# mainBoard_GRITSBot3-0_v14.net
KiCad netlist of a schematic drawn in EAGLE
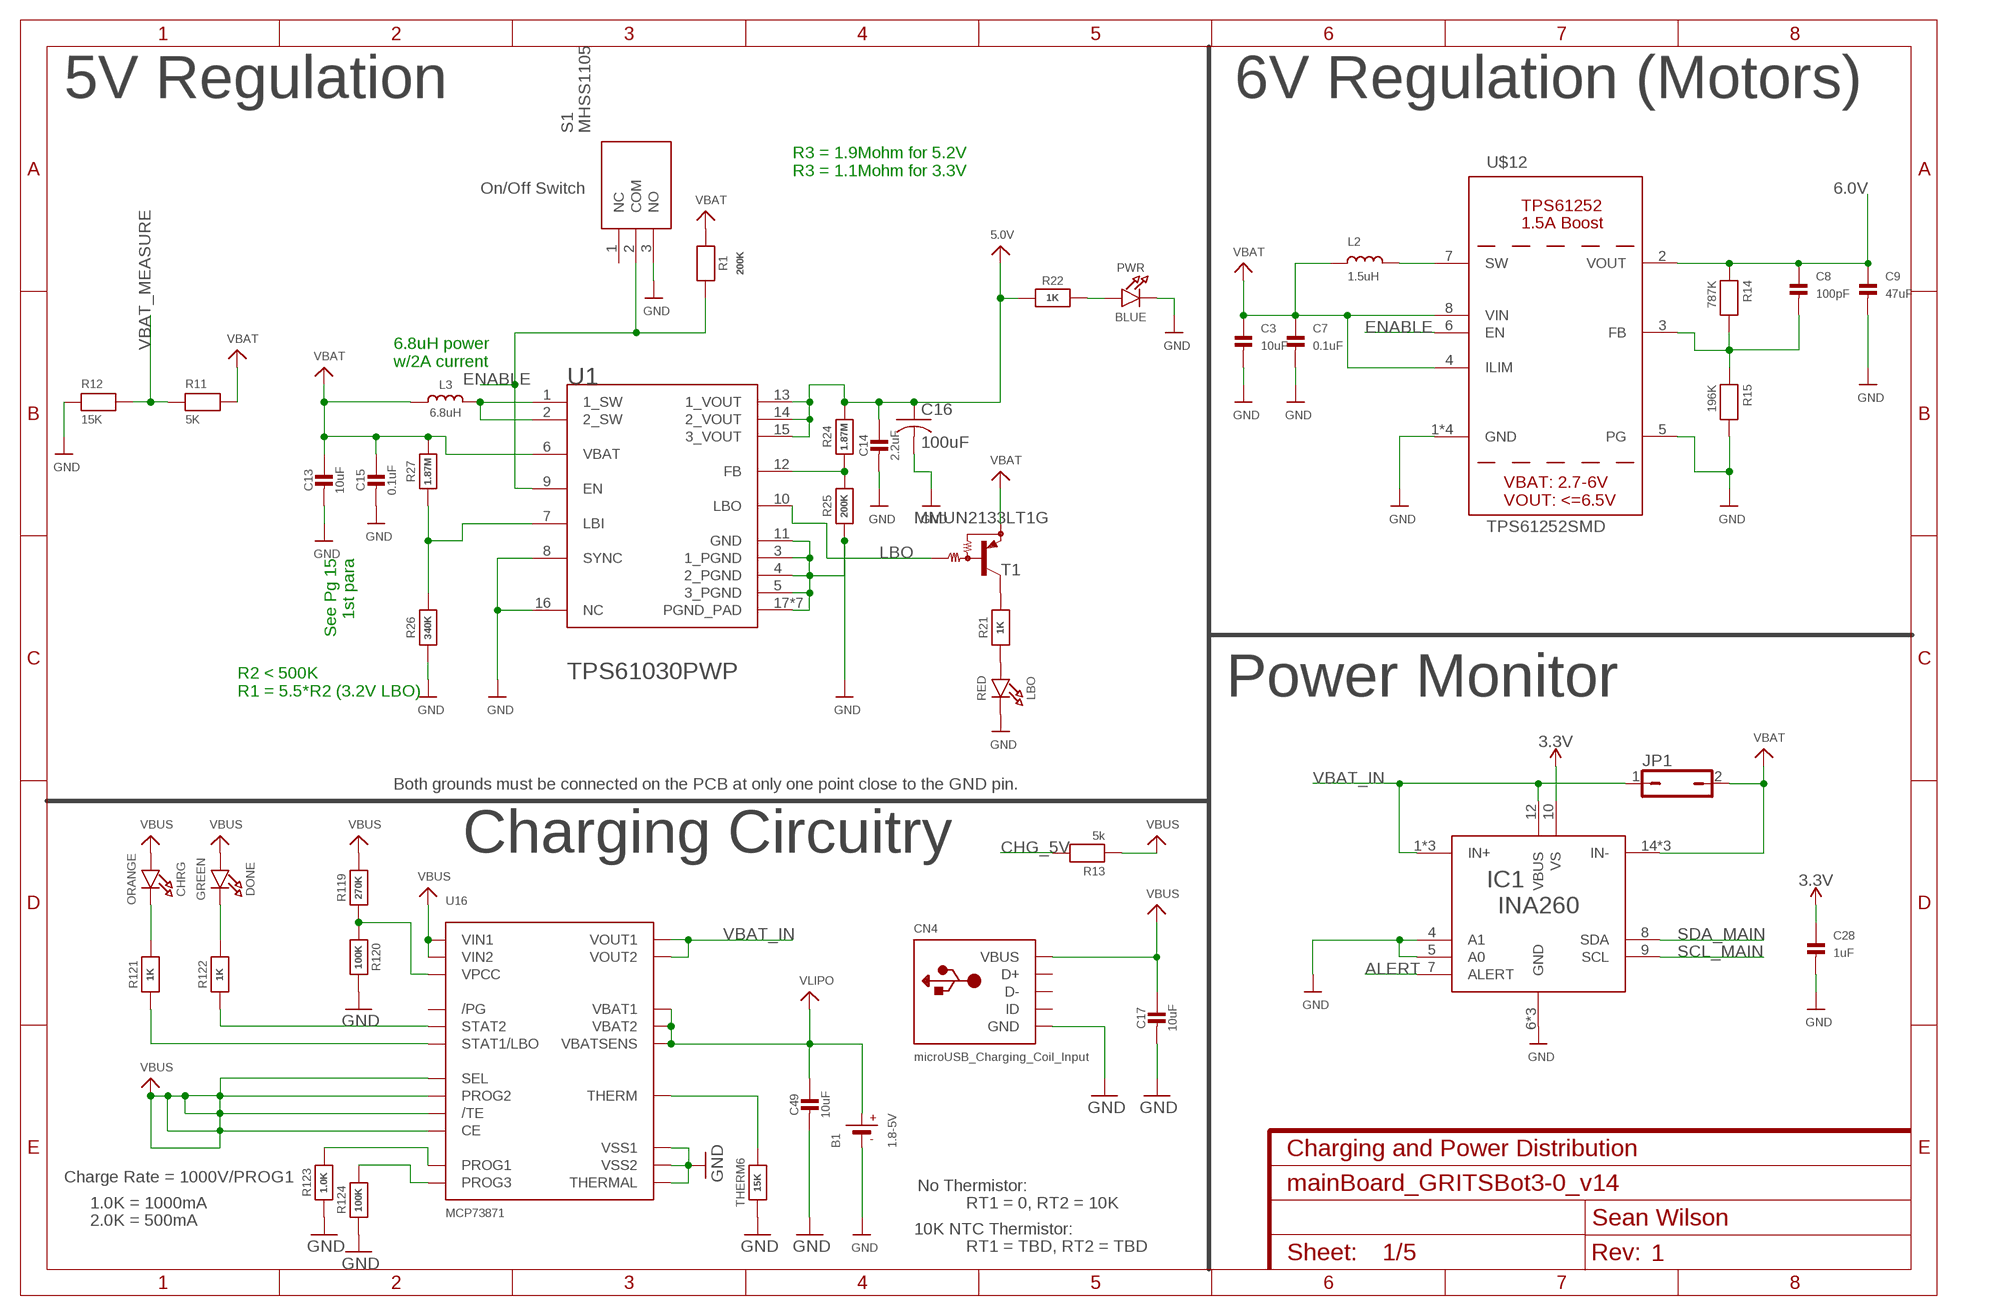
[diagram p0: schematic, sheet 1]
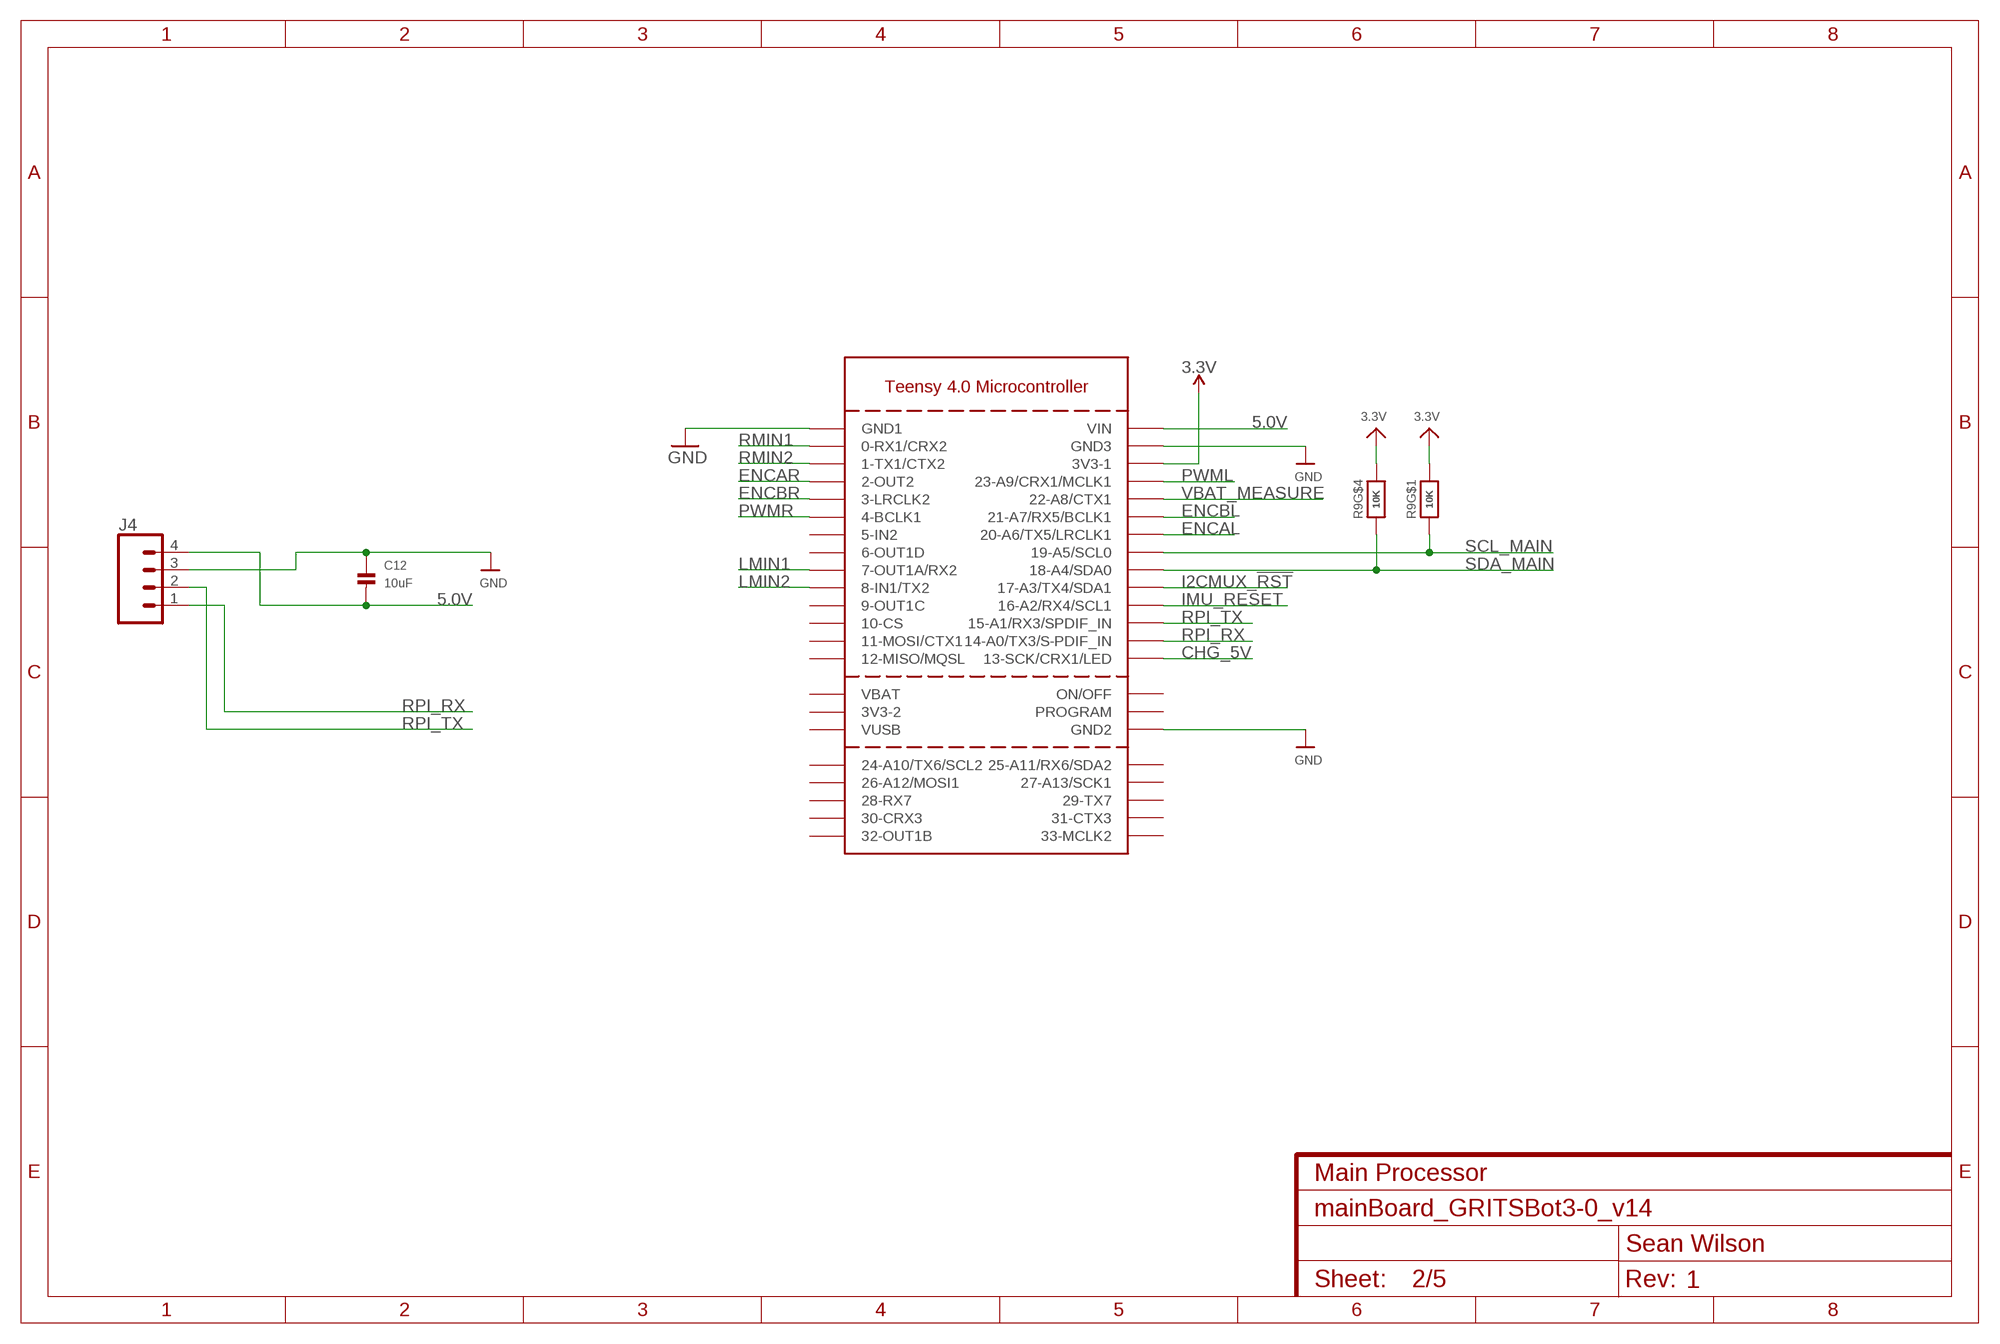
[diagram p1: schematic, sheet 2]
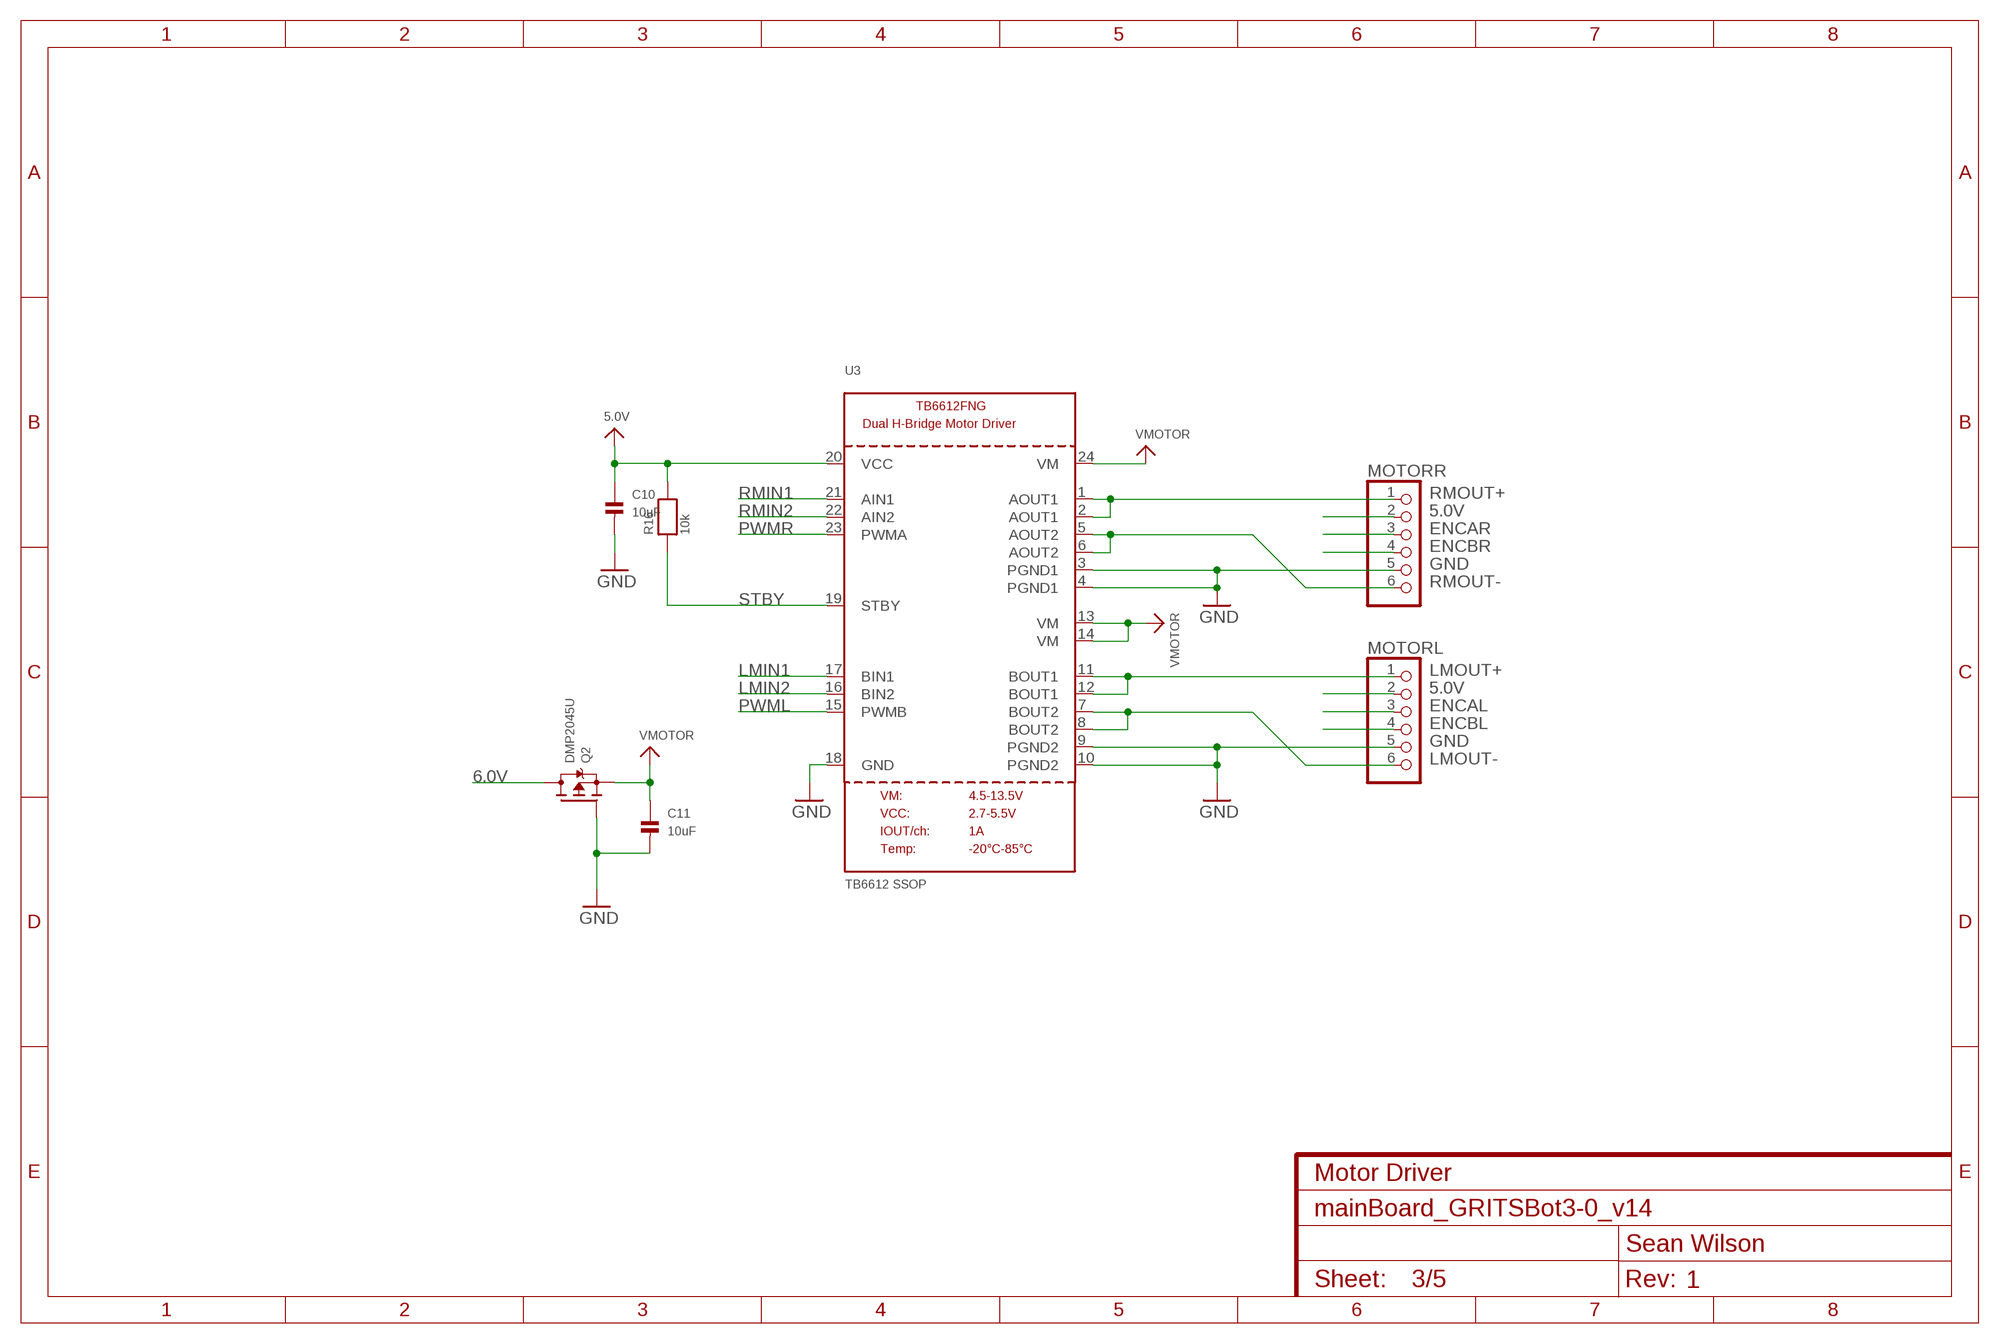
[diagram p2: schematic, sheet 3]
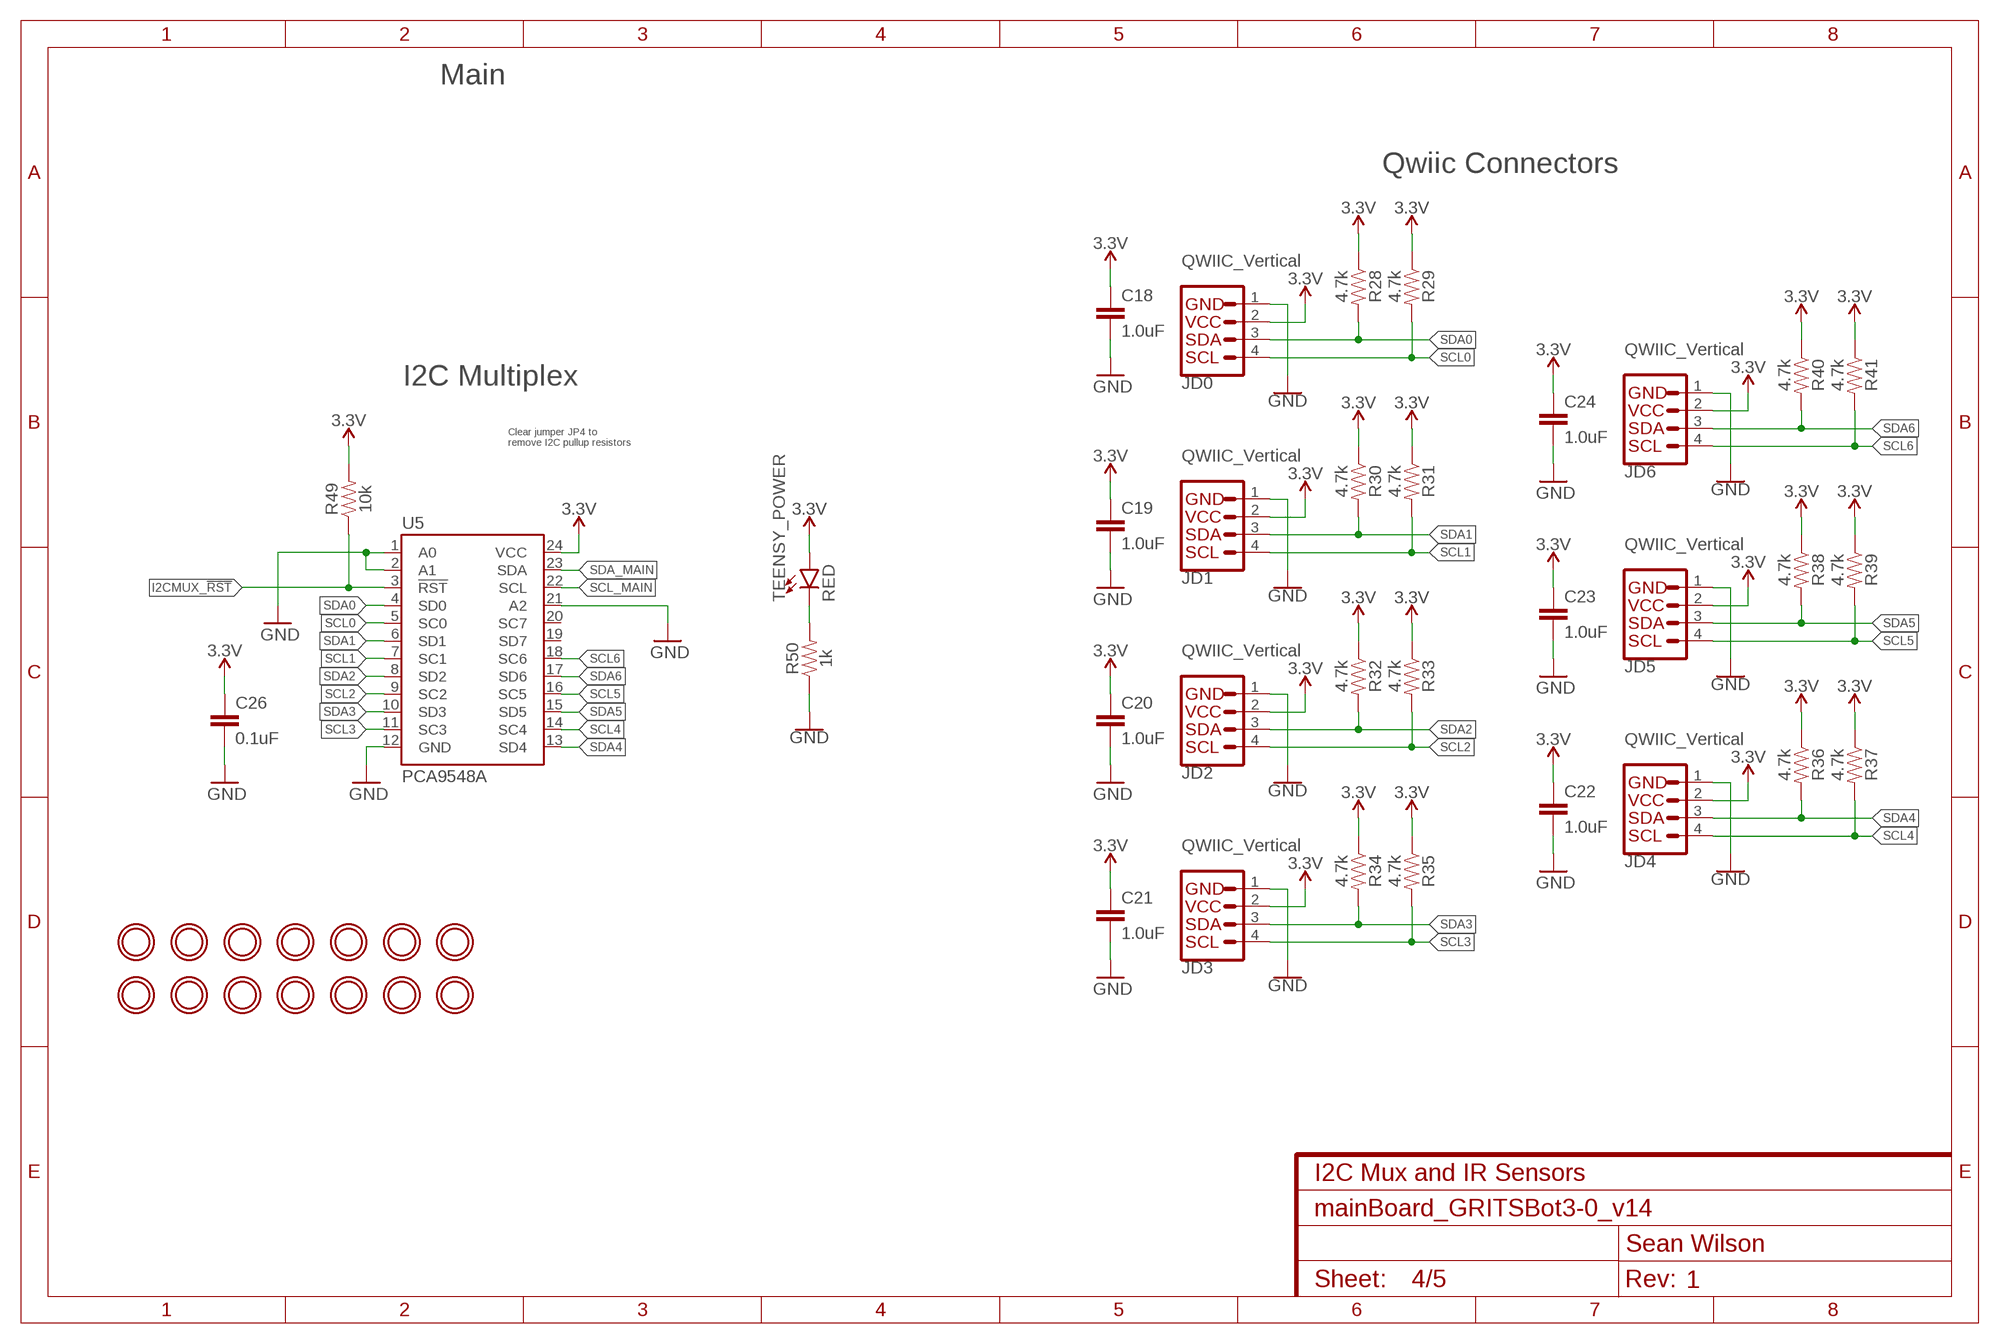
[diagram p3: schematic, sheet 4]
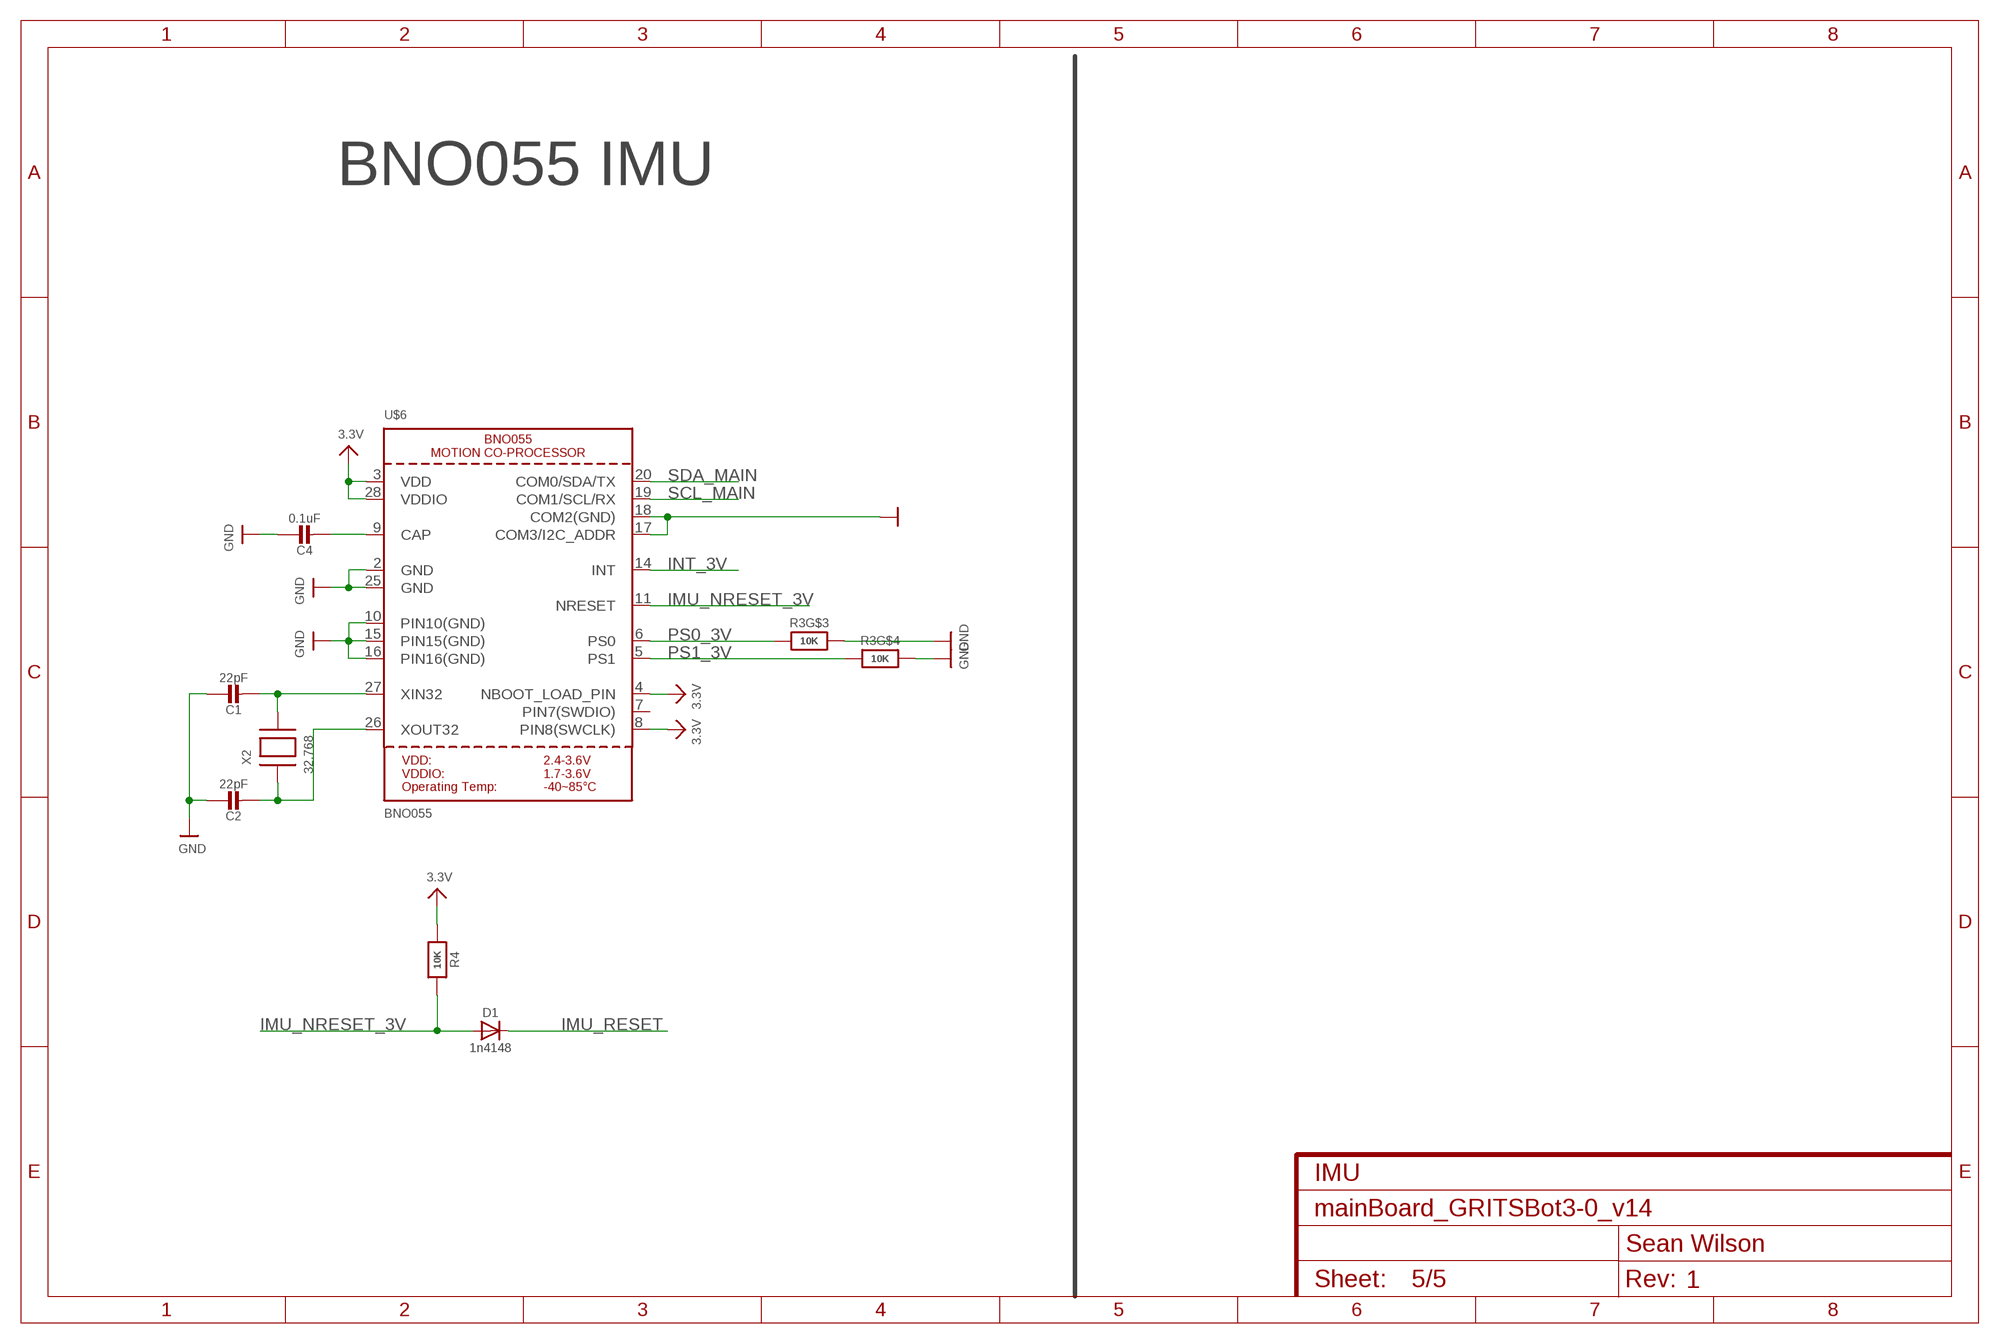
[diagram p4: schematic, sheet 5]

(export (version "E")
  (design (tool "Eeschema 10.0.6"))
  (components
    (comp (ref "C1")
      (value "22pF")
      (footprint "eagle-import:0603-NO")
      (libsource (lib "eagle-import") (part "CAP_CERAMIC0603_NO"))
    )
    (comp (ref "C2")
      (value "22pF")
      (footprint "eagle-import:0603-NO")
      (libsource (lib "eagle-import") (part "CAP_CERAMIC0603_NO"))
    )
    (comp (ref "C4")
      (value "0.1uF")
      (footprint "eagle-import:0603-NO")
      (libsource (lib "eagle-import") (part "CAP_CERAMIC0603_NO"))
    )
    (comp (ref "D1")
      (value "1n4148")
      (footprint "eagle-import:SOD-323")
      (libsource (lib "eagle-import") (part "DIODESOD-323"))
    )
    (comp (ref "R3")
      (value "10K")
      (footprint "eagle-import:RESPACK_4X0603")
      (libsource (lib "eagle-import") (part "RESISTOR_4PACK"))
    )
    (comp (ref "R4")
      (value "10K")
      (footprint "eagle-import:0603-NO")
      (libsource (lib "eagle-import") (part "RESISTOR_0603_NOOUT"))
    )
    (comp (ref "U$6")
      (value "BNO055")
      (footprint "eagle-import:BNO055")
      (libsource (lib "eagle-import") (part "BNO055"))
    )
    (comp (ref "X2")
      (value "32.768")
      (footprint "eagle-import:XTAL3215")
      (libsource (lib "eagle-import") (part "XTAL-3.2X1.5"))
    )
    (comp (ref "C12")
      (value "10uF")
      (footprint "eagle-import:0603")
      (libsource (lib "eagle-import") (part "CAP_CERAMIC0603"))
    )
    (comp (ref "J4")
      (value "CONN_041X04_NO_SILK")
      (footprint "eagle-import:1X04_NO_SILK")
      (libsource (lib "eagle-import") (part "CONN_041X04_NO_SILK"))
    )
    (comp (ref "R9")
      (value "10K")
      (footprint "eagle-import:RESPACK_4X0603")
      (libsource (lib "eagle-import") (part "RESISTOR_4PACK"))
    )
    (comp (ref "U$57")
      (value "TEENSY40")
      (footprint "eagle-import:TEENSY40")
      (libsource (lib "eagle-import") (part "TEENSY40"))
    )
    (comp (ref "C18")
      (value "1.0uF")
      (footprint "eagle-import:0603")
      (libsource (lib "eagle-import") (part "1.0UF-0603-16V-10%"))
    )
    (comp (ref "C19")
      (value "1.0uF")
      (footprint "eagle-import:0603")
      (libsource (lib "eagle-import") (part "1.0UF-0603-16V-10%"))
    )
    (comp (ref "C20")
      (value "1.0uF")
      (footprint "eagle-import:0603")
      (libsource (lib "eagle-import") (part "1.0UF-0603-16V-10%"))
    )
    (comp (ref "C21")
      (value "1.0uF")
      (footprint "eagle-import:0603")
      (libsource (lib "eagle-import") (part "1.0UF-0603-16V-10%"))
    )
    (comp (ref "C22")
      (value "1.0uF")
      (footprint "eagle-import:0603")
      (libsource (lib "eagle-import") (part "1.0UF-0603-16V-10%"))
    )
    (comp (ref "C23")
      (value "1.0uF")
      (footprint "eagle-import:0603")
      (libsource (lib "eagle-import") (part "1.0UF-0603-16V-10%"))
    )
    (comp (ref "C24")
      (value "1.0uF")
      (footprint "eagle-import:0603")
      (libsource (lib "eagle-import") (part "1.0UF-0603-16V-10%"))
    )
    (comp (ref "C26")
      (value "0.1uF")
      (footprint "eagle-import:0603")
      (libsource (lib "eagle-import") (part "0.1UF-0603-25V-(+80/-20%)"))
    )
    (comp (ref "JD0")
      (value "QWIIC_Vertical")
      (footprint "eagle-import:JST04_1MM_VERT")
      (libsource (lib "eagle-import") (part "QWIIC_CONNECTOR"))
    )
    (comp (ref "JD1")
      (value "QWIIC_Vertical")
      (footprint "eagle-import:JST04_1MM_VERT")
      (libsource (lib "eagle-import") (part "QWIIC_CONNECTOR"))
    )
    (comp (ref "JD2")
      (value "QWIIC_Vertical")
      (footprint "eagle-import:JST04_1MM_VERT")
      (libsource (lib "eagle-import") (part "QWIIC_CONNECTOR"))
    )
    (comp (ref "JD3")
      (value "QWIIC_Vertical")
      (footprint "eagle-import:JST04_1MM_VERT")
      (libsource (lib "eagle-import") (part "QWIIC_CONNECTOR"))
    )
    (comp (ref "JD4")
      (value "QWIIC_Vertical")
      (footprint "eagle-import:JST04_1MM_VERT")
      (libsource (lib "eagle-import") (part "QWIIC_CONNECTOR"))
    )
    (comp (ref "JD5")
      (value "QWIIC_Vertical")
      (footprint "eagle-import:JST04_1MM_VERT")
      (libsource (lib "eagle-import") (part "QWIIC_CONNECTOR"))
    )
    (comp (ref "JD6")
      (value "QWIIC_Vertical")
      (footprint "eagle-import:JST04_1MM_VERT")
      (libsource (lib "eagle-import") (part "QWIIC_CONNECTOR"))
    )
    (comp (ref "R28")
      (value "4.7k")
      (footprint "eagle-import:0603")
      (libsource (lib "eagle-import") (part "4.7KOHM-0603-1/10W-1%"))
    )
    (comp (ref "R29")
      (value "4.7k")
      (footprint "eagle-import:0603")
      (libsource (lib "eagle-import") (part "4.7KOHM-0603-1/10W-1%"))
    )
    (comp (ref "R30")
      (value "4.7k")
      (footprint "eagle-import:0603")
      (libsource (lib "eagle-import") (part "4.7KOHM-0603-1/10W-1%"))
    )
    (comp (ref "R31")
      (value "4.7k")
      (footprint "eagle-import:0603")
      (libsource (lib "eagle-import") (part "4.7KOHM-0603-1/10W-1%"))
    )
    (comp (ref "R32")
      (value "4.7k")
      (footprint "eagle-import:0603")
      (libsource (lib "eagle-import") (part "4.7KOHM-0603-1/10W-1%"))
    )
    (comp (ref "R33")
      (value "4.7k")
      (footprint "eagle-import:0603")
      (libsource (lib "eagle-import") (part "4.7KOHM-0603-1/10W-1%"))
    )
    (comp (ref "R34")
      (value "4.7k")
      (footprint "eagle-import:0603")
      (libsource (lib "eagle-import") (part "4.7KOHM-0603-1/10W-1%"))
    )
    (comp (ref "R35")
      (value "4.7k")
      (footprint "eagle-import:0603")
      (libsource (lib "eagle-import") (part "4.7KOHM-0603-1/10W-1%"))
    )
    (comp (ref "R36")
      (value "4.7k")
      (footprint "eagle-import:0603")
      (libsource (lib "eagle-import") (part "4.7KOHM-0603-1/10W-1%"))
    )
    (comp (ref "R37")
      (value "4.7k")
      (footprint "eagle-import:0603")
      (libsource (lib "eagle-import") (part "4.7KOHM-0603-1/10W-1%"))
    )
    (comp (ref "R38")
      (value "4.7k")
      (footprint "eagle-import:0603")
      (libsource (lib "eagle-import") (part "4.7KOHM-0603-1/10W-1%"))
    )
    (comp (ref "R39")
      (value "4.7k")
      (footprint "eagle-import:0603")
      (libsource (lib "eagle-import") (part "4.7KOHM-0603-1/10W-1%"))
    )
    (comp (ref "R40")
      (value "4.7k")
      (footprint "eagle-import:0603")
      (libsource (lib "eagle-import") (part "4.7KOHM-0603-1/10W-1%"))
    )
    (comp (ref "R41")
      (value "4.7k")
      (footprint "eagle-import:0603")
      (libsource (lib "eagle-import") (part "4.7KOHM-0603-1/10W-1%"))
    )
    (comp (ref "R49")
      (value "10k")
      (footprint "eagle-import:0603")
      (libsource (lib "eagle-import") (part "10KOHM-0603-1/10W-1%"))
    )
    (comp (ref "R50")
      (value "1k")
      (footprint "eagle-import:0603")
      (libsource (lib "eagle-import") (part "1KOHM-0603-1/10W-1%"))
    )
    (comp (ref "TEENSY_POWER")
      (value "RED")
      (footprint "eagle-import:LED-0603")
      (libsource (lib "eagle-import") (part "LED-RED0603"))
    )
    (comp (ref "U$8")
      (value "MOUNTINGHOLE2.5")
      (footprint "eagle-import:MOUNTINGHOLE_2.5_PLATED")
      (libsource (lib "eagle-import") (part "MOUNTINGHOLE2.5"))
    )
    (comp (ref "U$30")
      (value "MOUNTINGHOLE2.5")
      (footprint "eagle-import:MOUNTINGHOLE_2.5_PLATED")
      (libsource (lib "eagle-import") (part "MOUNTINGHOLE2.5"))
    )
    (comp (ref "U$31")
      (value "MOUNTINGHOLE2.5")
      (footprint "eagle-import:MOUNTINGHOLE_2.5_PLATED")
      (libsource (lib "eagle-import") (part "MOUNTINGHOLE2.5"))
    )
    (comp (ref "U$32")
      (value "MOUNTINGHOLE2.5")
      (footprint "eagle-import:MOUNTINGHOLE_2.5_PLATED")
      (libsource (lib "eagle-import") (part "MOUNTINGHOLE2.5"))
    )
    (comp (ref "U$33")
      (value "MOUNTINGHOLE2.5")
      (footprint "eagle-import:MOUNTINGHOLE_2.5_PLATED")
      (libsource (lib "eagle-import") (part "MOUNTINGHOLE2.5"))
    )
    (comp (ref "U$34")
      (value "MOUNTINGHOLE2.5")
      (footprint "eagle-import:MOUNTINGHOLE_2.5_PLATED")
      (libsource (lib "eagle-import") (part "MOUNTINGHOLE2.5"))
    )
    (comp (ref "U$35")
      (value "MOUNTINGHOLE2.5")
      (footprint "eagle-import:MOUNTINGHOLE_2.5_PLATED")
      (libsource (lib "eagle-import") (part "MOUNTINGHOLE2.5"))
    )
    (comp (ref "U$36")
      (value "MOUNTINGHOLE2.5")
      (footprint "eagle-import:MOUNTINGHOLE_2.5_PLATED")
      (libsource (lib "eagle-import") (part "MOUNTINGHOLE2.5"))
    )
    (comp (ref "U$37")
      (value "MOUNTINGHOLE2.5")
      (footprint "eagle-import:MOUNTINGHOLE_2.5_PLATED")
      (libsource (lib "eagle-import") (part "MOUNTINGHOLE2.5"))
    )
    (comp (ref "U$43")
      (value "MOUNTINGHOLE2.5")
      (footprint "eagle-import:MOUNTINGHOLE_2.5_PLATED")
      (libsource (lib "eagle-import") (part "MOUNTINGHOLE2.5"))
    )
    (comp (ref "U$45")
      (value "MOUNTINGHOLE2.5")
      (footprint "eagle-import:MOUNTINGHOLE_2.5_PLATED")
      (libsource (lib "eagle-import") (part "MOUNTINGHOLE2.5"))
    )
    (comp (ref "U$46")
      (value "MOUNTINGHOLE2.5")
      (footprint "eagle-import:MOUNTINGHOLE_2.5_PLATED")
      (libsource (lib "eagle-import") (part "MOUNTINGHOLE2.5"))
    )
    (comp (ref "U$47")
      (value "MOUNTINGHOLE2.5")
      (footprint "eagle-import:MOUNTINGHOLE_2.5_PLATED")
      (libsource (lib "eagle-import") (part "MOUNTINGHOLE2.5"))
    )
    (comp (ref "U$48")
      (value "MOUNTINGHOLE2.5")
      (footprint "eagle-import:MOUNTINGHOLE_2.5_PLATED")
      (libsource (lib "eagle-import") (part "MOUNTINGHOLE2.5"))
    )
    (comp (ref "U5")
      (value "PCA9548A")
      (footprint "eagle-import:TSSOP28")
      (libsource (lib "eagle-import") (part "PCA9548A"))
    )
    (comp (ref "B1")
      (value "1.8-5V")
      (footprint "eagle-import:JSTPH2")
      (libsource (lib "eagle-import") (part "BATTERY"))
    )
    (comp (ref "C3")
      (value "10uF")
      (footprint "eagle-import:0603")
      (libsource (lib "eagle-import") (part "CAP_CERAMIC0603"))
    )
    (comp (ref "C7")
      (value "0.1uF")
      (footprint "eagle-import:0805")
      (libsource (lib "eagle-import") (part "CAP_CERAMIC0805"))
    )
    (comp (ref "C8")
      (value "100pF")
      (footprint "eagle-import:0603")
      (libsource (lib "eagle-import") (part "CAP_CERAMIC0603"))
    )
    (comp (ref "C9")
      (value "47uF")
      (footprint "eagle-import:1206")
      (libsource (lib "eagle-import") (part "CAP_CERAMIC1206"))
    )
    (comp (ref "C13")
      (value "10uF")
      (footprint "eagle-import:0805-NO")
      (libsource (lib "eagle-import") (part "CAP_CERAMIC0805-NOOUTLINE"))
    )
    (comp (ref "C14")
      (value "2.2uF")
      (footprint "eagle-import:0805-NO")
      (libsource (lib "eagle-import") (part "CAP_CERAMIC0805-NOOUTLINE"))
    )
    (comp (ref "C15")
      (value "0.1uF")
      (footprint "eagle-import:0805_10MGAP")
      (libsource (lib "eagle-import") (part "CAP_CERAMIC0805_10MGAP"))
    )
    (comp (ref "C16")
      (value "100uF")
      (footprint "eagle-import:C1210")
      (libsource (lib "eagle-import") (part "C-USC1210"))
    )
    (comp (ref "C17")
      (value "10uF")
      (footprint "eagle-import:0805-NO")
      (libsource (lib "eagle-import") (part "CAP_CERAMIC0805-NOOUTLINE"))
    )
    (comp (ref "C28")
      (value "1uF")
      (footprint "eagle-import:0603-NO")
      (libsource (lib "eagle-import") (part "CAP_CERAMIC0603_NO"))
    )
    (comp (ref "C49")
      (value "10uF")
      (footprint "eagle-import:0805-NO")
      (libsource (lib "eagle-import") (part "CAP_CERAMIC0805-NOOUTLINE"))
    )
    (comp (ref "CHRG")
      (value "ORANGE")
      (footprint "eagle-import:CHIPLED_0805_NOOUTLINE")
      (libsource (lib "eagle-import") (part "LED0805_NOOUTLINE"))
    )
    (comp (ref "CN4")
      (value "microUSB_Charging_Coil_Input")
      (footprint "eagle-import:4UCONN_20329")
      (libsource (lib "eagle-import") (part "USBMICRO_20329"))
    )
    (comp (ref "DONE")
      (value "GREEN")
      (footprint "eagle-import:CHIPLED_0805_NOOUTLINE")
      (libsource (lib "eagle-import") (part "LED0805_NOOUTLINE"))
    )
    (comp (ref "IC1")
      (value "INA260")
      (footprint "eagle-import:TSSOP16")
      (libsource (lib "eagle-import") (part "INA260"))
    )
    (comp (ref "JP1")
      (value "JP1Q")
      (footprint "eagle-import:JP1")
      (libsource (lib "eagle-import") (part "JP1Q"))
    )
    (comp (ref "L2")
      (value "1.5uH")
      (footprint "eagle-import:MURATA_DFE252012P-1R5M=P2")
      (libsource (lib "eagle-import") (part "MURATA_DFE252012P-1R5M=P2"))
    )
    (comp (ref "L3")
      (value "6.8uH")
      (footprint "eagle-import:INDUCTOR_5X5MM_TDK_VLC5045")
      (libsource (lib "eagle-import") (part "INDUCTORTDK_VLC5045"))
    )
    (comp (ref "LBO")
      (value "RED")
      (footprint "eagle-import:CHIPLED_0805_NOOUTLINE")
      (libsource (lib "eagle-import") (part "LED0805_NOOUTLINE"))
    )
    (comp (ref "PWR")
      (value "BLUE")
      (footprint "eagle-import:CHIPLED_0805_NOOUTLINE")
      (libsource (lib "eagle-import") (part "LED0805_NOOUTLINE"))
    )
    (comp (ref "R1")
      (value "200K")
      (footprint "eagle-import:0805-NO")
      (libsource (lib "eagle-import") (part "RESISTOR0805_NOOUTLINE"))
    )
    (comp (ref "R11")
      (value "5K")
      (footprint "eagle-import:0805")
      (libsource (lib "eagle-import") (part "RESISTOR0805"))
    )
    (comp (ref "R12")
      (value "15K")
      (footprint "eagle-import:0805")
      (libsource (lib "eagle-import") (part "RESISTOR0805"))
    )
    (comp (ref "R13")
      (value "5k")
      (footprint "eagle-import:0805")
      (libsource (lib "eagle-import") (part "RESISTOR0805"))
    )
    (comp (ref "R14")
      (value "787K")
      (footprint "eagle-import:0805")
      (libsource (lib "eagle-import") (part "RESISTOR0805"))
    )
    (comp (ref "R15")
      (value "196K")
      (footprint "eagle-import:0805")
      (libsource (lib "eagle-import") (part "RESISTOR0805"))
    )
    (comp (ref "R21")
      (value "1K")
      (footprint "eagle-import:0805-NO")
      (libsource (lib "eagle-import") (part "RESISTOR0805_NOOUTLINE"))
    )
    (comp (ref "R22")
      (value "1K")
      (footprint "eagle-import:0805-NO")
      (libsource (lib "eagle-import") (part "RESISTOR0805_NOOUTLINE"))
    )
    (comp (ref "R24")
      (value "1.87M")
      (footprint "eagle-import:0805-NO")
      (libsource (lib "eagle-import") (part "RESISTOR0805_NOOUTLINE"))
    )
    (comp (ref "R25")
      (value "200K")
      (footprint "eagle-import:0805-NO")
      (libsource (lib "eagle-import") (part "RESISTOR0805_NOOUTLINE"))
    )
    (comp (ref "R26")
      (value "340K")
      (footprint "eagle-import:_0805MP")
      (libsource (lib "eagle-import") (part "microbuilder_vf.jQhFfLl6SwyupizEU6PNDA_RESISTOR_0805MP"))
    )
    (comp (ref "R27")
      (value "1.87M")
      (footprint "eagle-import:_0805MP")
      (libsource (lib "eagle-import") (part "microbuilder_vf.jQhFfLl6SwyupizEU6PNDA_RESISTOR_0805MP"))
    )
    (comp (ref "R119")
      (value "270K")
      (footprint "eagle-import:0805-NO")
      (libsource (lib "eagle-import") (part "RESISTOR0805_NOOUTLINE"))
    )
    (comp (ref "R120")
      (value "100K")
      (footprint "eagle-import:0805-NO")
      (libsource (lib "eagle-import") (part "RESISTOR0805_NOOUTLINE"))
    )
    (comp (ref "R121")
      (value "1K")
      (footprint "eagle-import:0805-NO")
      (libsource (lib "eagle-import") (part "RESISTOR0805_NOOUTLINE"))
    )
    (comp (ref "R122")
      (value "1K")
      (footprint "eagle-import:0805-NO")
      (libsource (lib "eagle-import") (part "RESISTOR0805_NOOUTLINE"))
    )
    (comp (ref "R123")
      (value "1.0K")
      (footprint "eagle-import:0805-NO")
      (libsource (lib "eagle-import") (part "RESISTOR0805_NOOUTLINE"))
    )
    (comp (ref "R124")
      (value "100K")
      (footprint "eagle-import:0805-NO")
      (libsource (lib "eagle-import") (part "RESISTOR0805_NOOUTLINE"))
    )
    (comp (ref "S1")
      (value "MHSS1105")
      (footprint "eagle-import:MHSS1105")
      (fields (field (name "MOUSER_PART_NUMBER") "642-MHSS1105"))
      (libsource (lib "eagle-import") (part "MHSS1105"))
    )
    (comp (ref "T1")
      (value "MMUN2133LT1G")
      (footprint "eagle-import:SC59-BEC")
      (libsource (lib "eagle-import") (part "-PNP_DRIVER-SC59-BECMUN2114T1"))
    )
    (comp (ref "THERM6")
      (value "15K")
      (footprint "eagle-import:0805-NO")
      (libsource (lib "eagle-import") (part "RESISTOR0805_NOOUTLINE"))
    )
    (comp (ref "U$12")
      (value "TPS61252SMD")
      (footprint "eagle-import:TPS61252")
      (libsource (lib "eagle-import") (part "TPS61252SMD"))
    )
    (comp (ref "U1")
      (value "TEXAS_INSTRUMENTS_TPS61030PWPTEXAS_INSTRUMENTS_TPS61030PWP_0_0")
      (footprint "eagle-import:TEXAS_INSTRUMENTS_TPS61030PWP_0")
      (fields
        (field (name "DIGIKEY_PART_NUMBER") "296-27006-5-ND")
        (field (name "MF") "Texas Instruments")
        (field (name "MOUSER_PART_NUMBER") "595-TPS61030PWP")
      )
      (libsource (lib "eagle-import") (part "TEXAS_INSTRUMENTS_TPS61030PWPTEXAS_INSTRUMENTS_TPS61030PWP_0_0"))
    )
    (comp (ref "U16")
      (value "MCP73871")
      (footprint "eagle-import:QFN20_4MM")
      (libsource (lib "eagle-import") (part "MCP73871"))
    )
    (comp (ref "C10")
      (value "10uF")
      (footprint "eagle-import:0603")
      (libsource (lib "eagle-import") (part "CAP_CERAMIC0603"))
    )
    (comp (ref "C11")
      (value "10uF")
      (footprint "eagle-import:0603")
      (libsource (lib "eagle-import") (part "CAP_CERAMIC0603"))
    )
    (comp (ref "MOTORL")
      (value "PINHD-1X6CB")
      (footprint "eagle-import:1X06-CLEANBIG")
      (libsource (lib "eagle-import") (part "PINHD-1X6CB"))
    )
    (comp (ref "MOTORR")
      (value "PINHD-1X6CB")
      (footprint "eagle-import:1X06-CLEANBIG")
      (libsource (lib "eagle-import") (part "PINHD-1X6CB"))
    )
    (comp (ref "Q2")
      (value "DMP2045U")
      (footprint "eagle-import:SOT23-WIDE")
      (libsource (lib "eagle-import") (part "MOSFET-PWIDE"))
    )
    (comp (ref "R16")
      (value "10k")
      (footprint "eagle-import:0805")
      (libsource (lib "eagle-import") (part "RESISTOR0805"))
    )
    (comp (ref "U3")
      (value "TB6612 SSOP")
      (footprint "eagle-import:SSOP24")
      (libsource (lib "eagle-import") (part "TB6612FNGSSOP"))
    )
  )
  (nets
    (net (code "1") (name "3.3V") (class "Default")
      (node (ref "C18") (pin "1") (pinfunction "1_1") (pintype "passive"))
      (node (ref "C19") (pin "1") (pinfunction "1_1") (pintype "passive"))
      (node (ref "C20") (pin "1") (pinfunction "1_1") (pintype "passive"))
      (node (ref "C21") (pin "1") (pinfunction "1_1") (pintype "passive"))
      (node (ref "C22") (pin "1") (pinfunction "1_1") (pintype "passive"))
      (node (ref "C23") (pin "1") (pinfunction "1_1") (pintype "passive"))
      (node (ref "C24") (pin "1") (pinfunction "1_1") (pintype "passive"))
      (node (ref "C26") (pin "1") (pinfunction "1_1") (pintype "passive"))
      (node (ref "C28") (pin "1") (pinfunction "1_1") (pintype "passive"))
      (node (ref "IC1") (pin "10") (pinfunction "VS_10") (pintype "power_in"))
      (node (ref "JD0") (pin "2") (pinfunction "2_2") (pintype "power_in"))
      (node (ref "JD1") (pin "2") (pinfunction "2_2") (pintype "power_in"))
      (node (ref "JD2") (pin "2") (pinfunction "2_2") (pintype "power_in"))
      (node (ref "JD3") (pin "2") (pinfunction "2_2") (pintype "power_in"))
      (node (ref "JD4") (pin "2") (pinfunction "2_2") (pintype "power_in"))
      (node (ref "JD5") (pin "2") (pinfunction "2_2") (pintype "power_in"))
      (node (ref "JD6") (pin "2") (pinfunction "2_2") (pintype "power_in"))
      (node (ref "R28") (pin "1") (pinfunction "1_1") (pintype "passive"))
      (node (ref "R29") (pin "1") (pinfunction "1_1") (pintype "passive"))
      (node (ref "R30") (pin "1") (pinfunction "1_1") (pintype "passive"))
      (node (ref "R31") (pin "1") (pinfunction "1_1") (pintype "passive"))
      (node (ref "R32") (pin "1") (pinfunction "1_1") (pintype "passive"))
      (node (ref "R33") (pin "1") (pinfunction "1_1") (pintype "passive"))
      (node (ref "R34") (pin "1") (pinfunction "1_1") (pintype "passive"))
      (node (ref "R35") (pin "1") (pinfunction "1_1") (pintype "passive"))
      (node (ref "R36") (pin "1") (pinfunction "1_1") (pintype "passive"))
      (node (ref "R37") (pin "1") (pinfunction "1_1") (pintype "passive"))
      (node (ref "R38") (pin "1") (pinfunction "1_1") (pintype "passive"))
      (node (ref "R39") (pin "1") (pinfunction "1_1") (pintype "passive"))
      (node (ref "R4") (pin "1") (pinfunction "1_1") (pintype "passive"))
      (node (ref "R40") (pin "1") (pinfunction "1_1") (pintype "passive"))
      (node (ref "R41") (pin "1") (pinfunction "1_1") (pintype "passive"))
      (node (ref "R49") (pin "2") (pinfunction "2_2") (pintype "passive"))
      (node (ref "R9") (pin "1") (pinfunction "1_1") (pintype "passive"))
      (node (ref "R9") (pin "4") (pinfunction "1_4") (pintype "passive"))
      (node (ref "TEENSY_POWER") (pin "A") (pinfunction "A_A") (pintype "passive"))
      (node (ref "U$57") (pin "3V3-1") (pinfunction "3V3-1_3V3-1") (pintype "bidirectional"))
      (node (ref "U$6") (pin "28") (pinfunction "VDDIO_28") (pintype "power_in"))
      (node (ref "U$6") (pin "3") (pinfunction "VDD_3") (pintype "power_in"))
      (node (ref "U$6") (pin "4") (pinfunction "NBOOT_LOAD_PIN_4") (pintype "bidirectional"))
      (node (ref "U$6") (pin "8") (pinfunction "PIN8(SWCLK)_8") (pintype "bidirectional"))
      (node (ref "U5") (pin "24") (pinfunction "VCC_24") (pintype "bidirectional"))
    )
    (net (code "2") (name "5.0V") (class "Default")
      (node (ref "C10") (pin "1") (pinfunction "P$1_1") (pintype "passive"))
      (node (ref "C12") (pin "2") (pinfunction "P$2_2") (pintype "passive"))
      (node (ref "C14") (pin "1") (pinfunction "1_1") (pintype "passive"))
      (node (ref "C16") (pin "1") (pinfunction "1_1") (pintype "passive"))
      (node (ref "J4") (pin "4") (pinfunction "4_4") (pintype "passive"))
      (node (ref "MOTORL") (pin "2") (pinfunction "2_2") (pintype "passive"))
      (node (ref "MOTORR") (pin "2") (pinfunction "2_2") (pintype "passive"))
      (node (ref "R16") (pin "2") (pinfunction "2_2") (pintype "passive"))
      (node (ref "R22") (pin "1") (pinfunction "1_1") (pintype "passive"))
      (node (ref "R24") (pin "2") (pinfunction "2_2") (pintype "passive"))
      (node (ref "U$57") (pin "VIN") (pinfunction "VIN_VIN") (pintype "bidirectional"))
      (node (ref "U1") (pin "13") (pinfunction "1_VOUT_13") (pintype "bidirectional"))
      (node (ref "U1") (pin "14") (pinfunction "2_VOUT_14") (pintype "bidirectional"))
      (node (ref "U1") (pin "15") (pinfunction "3_VOUT_15") (pintype "bidirectional"))
      (node (ref "U3") (pin "20") (pinfunction "VCC_20") (pintype "power_in"))
    )
    (net (code "3") (name "6.0V") (class "Default")
      (node (ref "C8") (pin "1") (pinfunction "P$1_1") (pintype "passive"))
      (node (ref "C9") (pin "1") (pinfunction "P$1_1") (pintype "passive"))
      (node (ref "Q2") (pin "3") (pinfunction "D_3") (pintype "passive"))
      (node (ref "R14") (pin "1") (pinfunction "1_1") (pintype "passive"))
      (node (ref "U$12") (pin "2") (pinfunction "VOUT_2") (pintype "bidirectional"))
    )
    (net (code "4") (name "ALERT") (class "Default")
      (node (ref "IC1") (pin "7") (pinfunction "ALERT_7") (pintype "output"))
    )
    (net (code "5") (name "CHG_5V") (class "Default")
      (node (ref "R13") (pin "2") (pinfunction "2_2") (pintype "passive"))
      (node (ref "U$57") (pin "13-SCK/CRX1/LED") (pinfunction "13-SCK/CRX1/LED_13-SCK/CRX1/LED") (pintype "bidirectional"))
    )
    (net (code "6") (name "ENABLE") (class "Default")
      (node (ref "R1") (pin "2") (pinfunction "2_2") (pintype "passive"))
      (node (ref "S1") (pin "2") (pinfunction "COM_2") (pintype "bidirectional"))
      (node (ref "U$12") (pin "6") (pinfunction "EN_6") (pintype "bidirectional"))
      (node (ref "U1") (pin "9") (pinfunction "EN_9") (pintype "bidirectional"))
    )
    (net (code "7") (name "ENCAL") (class "Default")
      (node (ref "MOTORL") (pin "3") (pinfunction "3_3") (pintype "passive"))
      (node (ref "U$57") (pin "20-A6/TX5/LRCLK1") (pinfunction "20-A6/TX5/LRCLK1_20-A6/TX5/LRCLK1") (pintype "bidirectional"))
    )
    (net (code "8") (name "ENCAR") (class "Default")
      (node (ref "MOTORR") (pin "3") (pinfunction "3_3") (pintype "passive"))
      (node (ref "U$57") (pin "2-OUT2") (pinfunction "2-OUT2_2-OUT2") (pintype "bidirectional"))
    )
    (net (code "9") (name "ENCBL") (class "Default")
      (node (ref "MOTORL") (pin "4") (pinfunction "4_4") (pintype "passive"))
      (node (ref "U$57") (pin "21-A7/RX5/BCLK1") (pinfunction "21-A7/RX5/BCLK1_21-A7/RX5/BCLK1") (pintype "bidirectional"))
    )
    (net (code "10") (name "ENCBR") (class "Default")
      (node (ref "MOTORR") (pin "4") (pinfunction "4_4") (pintype "passive"))
      (node (ref "U$57") (pin "3-LRCLK2") (pinfunction "3-LRCLK2_3-LRCLK2") (pintype "bidirectional"))
    )
    (net (code "11") (name "GND") (class "Default")
      (node (ref "B1") (pin "1") (pinfunction "-_1") (pintype "passive"))
      (node (ref "C1") (pin "1") (pinfunction "1_1") (pintype "passive"))
      (node (ref "C10") (pin "2") (pinfunction "P$2_2") (pintype "passive"))
      (node (ref "C11") (pin "2") (pinfunction "P$2_2") (pintype "passive"))
      (node (ref "C12") (pin "1") (pinfunction "P$1_1") (pintype "passive"))
      (node (ref "C13") (pin "2") (pinfunction "2_2") (pintype "passive"))
      (node (ref "C14") (pin "2") (pinfunction "2_2") (pintype "passive"))
      (node (ref "C15") (pin "2") (pinfunction "2_2") (pintype "passive"))
      (node (ref "C16") (pin "2") (pinfunction "2_2") (pintype "passive"))
      (node (ref "C17") (pin "2") (pinfunction "2_2") (pintype "passive"))
      (node (ref "C18") (pin "2") (pinfunction "2_2") (pintype "passive"))
      (node (ref "C19") (pin "2") (pinfunction "2_2") (pintype "passive"))
      (node (ref "C2") (pin "1") (pinfunction "1_1") (pintype "passive"))
      (node (ref "C20") (pin "2") (pinfunction "2_2") (pintype "passive"))
      (node (ref "C21") (pin "2") (pinfunction "2_2") (pintype "passive"))
      (node (ref "C22") (pin "2") (pinfunction "2_2") (pintype "passive"))
      (node (ref "C23") (pin "2") (pinfunction "2_2") (pintype "passive"))
      (node (ref "C24") (pin "2") (pinfunction "2_2") (pintype "passive"))
      (node (ref "C26") (pin "2") (pinfunction "2_2") (pintype "passive"))
      (node (ref "C28") (pin "2") (pinfunction "2_2") (pintype "passive"))
      (node (ref "C3") (pin "2") (pinfunction "P$2_2") (pintype "passive"))
      (node (ref "C4") (pin "1") (pinfunction "1_1") (pintype "passive"))
      (node (ref "C49") (pin "2") (pinfunction "2_2") (pintype "passive"))
      (node (ref "C7") (pin "2") (pinfunction "P$2_2") (pintype "passive"))
      (node (ref "C9") (pin "2") (pinfunction "P$2_2") (pintype "passive"))
      (node (ref "CN4") (pin "BASE@1") (pinfunction "GND_BASE@1") (pintype "power_in"))
      (node (ref "CN4") (pin "BASE@2") (pinfunction "GND_BASE@2") (pintype "power_in"))
      (node (ref "CN4") (pin "GND") (pinfunction "GND_GND") (pintype "power_in"))
      (node (ref "CN4") (pin "SPRT@1") (pinfunction "GND_SPRT@1") (pintype "power_in"))
      (node (ref "CN4") (pin "SPRT@2") (pinfunction "GND_SPRT@2") (pintype "power_in"))
      (node (ref "CN4") (pin "SPRT@3") (pinfunction "GND_SPRT@3") (pintype "power_in"))
      (node (ref "CN4") (pin "SPRT@4") (pinfunction "GND_SPRT@4") (pintype "power_in"))
      (node (ref "IC1") (pin "11") (pinfunction "GND_11") (pintype "power_in"))
      (node (ref "IC1") (pin "13") (pinfunction "GND_13") (pintype "power_in"))
      (node (ref "IC1") (pin "4") (pinfunction "A1_4") (pintype "input"))
      (node (ref "IC1") (pin "5") (pinfunction "A0_5") (pintype "input"))
      (node (ref "IC1") (pin "6") (pinfunction "GND_6") (pintype "power_in"))
      (node (ref "J4") (pin "3") (pinfunction "3_3") (pintype "passive"))
      (node (ref "JD0") (pin "1") (pinfunction "1_1") (pintype "power_in"))
      (node (ref "JD1") (pin "1") (pinfunction "1_1") (pintype "power_in"))
      (node (ref "JD2") (pin "1") (pinfunction "1_1") (pintype "power_in"))
      (node (ref "JD3") (pin "1") (pinfunction "1_1") (pintype "power_in"))
      (node (ref "JD4") (pin "1") (pinfunction "1_1") (pintype "power_in"))
      (node (ref "JD5") (pin "1") (pinfunction "1_1") (pintype "power_in"))
      (node (ref "JD6") (pin "1") (pinfunction "1_1") (pintype "power_in"))
      (node (ref "LBO") (pin "C") (pinfunction "C_C") (pintype "passive"))
      (node (ref "MOTORL") (pin "5") (pinfunction "5_5") (pintype "passive"))
      (node (ref "MOTORR") (pin "5") (pinfunction "5_5") (pintype "passive"))
      (node (ref "PWR") (pin "C") (pinfunction "C_C") (pintype "passive"))
      (node (ref "Q2") (pin "1") (pinfunction "G_1") (pintype "passive"))
      (node (ref "R12") (pin "1") (pinfunction "1_1") (pintype "passive"))
      (node (ref "R120") (pin "2") (pinfunction "2_2") (pintype "passive"))
      (node (ref "R123") (pin "1") (pinfunction "1_1") (pintype "passive"))
      (node (ref "R124") (pin "1") (pinfunction "1_1") (pintype "passive"))
      (node (ref "R15") (pin "2") (pinfunction "2_2") (pintype "passive"))
      (node (ref "R25") (pin "1") (pinfunction "1_1") (pintype "passive"))
      (node (ref "R26") (pin "1") (pinfunction "1_1") (pintype "passive"))
      (node (ref "R3") (pin "5") (pinfunction "2_5") (pintype "passive"))
      (node (ref "R3") (pin "6") (pinfunction "2_6") (pintype "passive"))
      (node (ref "R50") (pin "1") (pinfunction "1_1") (pintype "passive"))
      (node (ref "S1") (pin "3") (pinfunction "NO_3") (pintype "bidirectional"))
      (node (ref "THERM6") (pin "1") (pinfunction "1_1") (pintype "passive"))
      (node (ref "U$12") (pin "1") (pinfunction "GND_1") (pintype "bidirectional"))
      (node (ref "U$12") (pin "5") (pinfunction "PG_5") (pintype "bidirectional"))
      (node (ref "U$12") (pin "P$2_GND") (pinfunction "GND_P$2_GND") (pintype "bidirectional"))
      (node (ref "U$12") (pin "P$3_GND") (pinfunction "GND_P$3_GND") (pintype "bidirectional"))
      (node (ref "U$12") (pin "THERMAL_GND") (pinfunction "GND_THERMAL_GND") (pintype "bidirectional"))
      (node (ref "U$57") (pin "GND1") (pinfunction "GND1_GND1") (pintype "bidirectional"))
      (node (ref "U$57") (pin "GND2") (pinfunction "GND2_GND2") (pintype "bidirectional"))
      (node (ref "U$57") (pin "GND3") (pinfunction "GND3_GND3") (pintype "bidirectional"))
      (node (ref "U$6") (pin "10") (pinfunction "PIN10(GND)_10") (pintype "bidirectional"))
      (node (ref "U$6") (pin "15") (pinfunction "PIN15(GND)_15") (pintype "bidirectional"))
      (node (ref "U$6") (pin "16") (pinfunction "PIN16(GND)_16") (pintype "bidirectional"))
      (node (ref "U$6") (pin "17") (pinfunction "COM3/I2C_ADDR_17") (pintype "bidirectional"))
      (node (ref "U$6") (pin "18") (pinfunction "COM2(GND)_18") (pintype "bidirectional"))
      (node (ref "U$6") (pin "2") (pinfunction "GND_2") (pintype "power_in"))
      (node (ref "U$6") (pin "25") (pinfunction "GND_25") (pintype "power_in"))
      (node (ref "U1") (pin "11") (pinfunction "GND_11") (pintype "bidirectional"))
      (node (ref "U1") (pin "16") (pinfunction "NC_16") (pintype "bidirectional"))
      (node (ref "U1") (pin "17") (pinfunction "PGND_PAD_17") (pintype "bidirectional"))
      (node (ref "U1") (pin "3") (pinfunction "1_PGND_3") (pintype "bidirectional"))
      (node (ref "U1") (pin "4") (pinfunction "2_PGND_4") (pintype "bidirectional"))
      (node (ref "U1") (pin "5") (pinfunction "3_PGND_5") (pintype "bidirectional"))
      (node (ref "U1") (pin "8") (pinfunction "SYNC_8") (pintype "bidirectional"))
      (node (ref "U1") (pin "PAD_1") (pinfunction "PGND_PAD_PAD_1") (pintype "bidirectional"))
      (node (ref "U1") (pin "PAD_2") (pinfunction "PGND_PAD_PAD_2") (pintype "bidirectional"))
      (node (ref "U1") (pin "PAD_3") (pinfunction "PGND_PAD_PAD_3") (pintype "bidirectional"))
      (node (ref "U1") (pin "PAD_4") (pinfunction "PGND_PAD_PAD_4") (pintype "bidirectional"))
      (node (ref "U1") (pin "PAD_5") (pinfunction "PGND_PAD_PAD_5") (pintype "bidirectional"))
      (node (ref "U1") (pin "PAD_6") (pinfunction "PGND_PAD_PAD_6") (pintype "bidirectional"))
      (node (ref "U16") (pin "P$10") (pinfunction "VSS1_P$10") (pintype "bidirectional"))
      (node (ref "U16") (pin "P$11") (pinfunction "VSS2_P$11") (pintype "bidirectional"))
      (node (ref "U16") (pin "P$21") (pinfunction "THERMAL_P$21") (pintype "bidirectional"))
      (node (ref "U3") (pin "10") (pinfunction "PGND2_10") (pintype "power_in"))
      (node (ref "U3") (pin "18") (pinfunction "GND_18") (pintype "power_in"))
      (node (ref "U3") (pin "3") (pinfunction "PGND1_3") (pintype "power_in"))
      (node (ref "U3") (pin "4") (pinfunction "PGND1_4") (pintype "power_in"))
      (node (ref "U3") (pin "9") (pinfunction "PGND2_9") (pintype "power_in"))
      (node (ref "U5") (pin "1") (pinfunction "A0_1") (pintype "bidirectional"))
      (node (ref "U5") (pin "12") (pinfunction "GND_12") (pintype "bidirectional"))
      (node (ref "U5") (pin "2") (pinfunction "A1_2") (pintype "bidirectional"))
      (node (ref "U5") (pin "21") (pinfunction "A2_21") (pintype "bidirectional"))
    )
    (net (code "12") (name "I2CMUX_~{RST}") (class "Default")
      (node (ref "R49") (pin "1") (pinfunction "1_1") (pintype "passive"))
      (node (ref "U$57") (pin "17-A3/TX4/SDA1") (pinfunction "17-A3/TX4/SDA1_17-A3/TX4/SDA1") (pintype "bidirectional"))
      (node (ref "U5") (pin "3") (pinfunction "~{RST}_3") (pintype "bidirectional"))
    )
    (net (code "13") (name "IMU_NRESET_3V") (class "Default")
      (node (ref "D1") (pin "A") (pinfunction "A_A") (pintype "passive"))
      (node (ref "R4") (pin "2") (pinfunction "2_2") (pintype "passive"))
      (node (ref "U$6") (pin "11") (pinfunction "NRESET_11") (pintype "bidirectional"))
    )
    (net (code "14") (name "IMU_RESET") (class "Default")
      (node (ref "D1") (pin "C") (pinfunction "C_C") (pintype "passive"))
      (node (ref "U$57") (pin "16-A2/RX4/SCL1") (pinfunction "16-A2/RX4/SCL1_16-A2/RX4/SCL1") (pintype "bidirectional"))
    )
    (net (code "15") (name "INT_3V") (class "Default")
      (node (ref "U$6") (pin "14") (pinfunction "INT_14") (pintype "output"))
    )
    (net (code "16") (name "LBO") (class "Default")
      (node (ref "T1") (pin "B") (pinfunction "B_B") (pintype "passive"))
      (node (ref "U1") (pin "10") (pinfunction "LBO_10") (pintype "bidirectional"))
    )
    (net (code "17") (name "LMIN1") (class "Default")
      (node (ref "U$57") (pin "7-RX2/OUT1A") (pinfunction "7-OUT1A/RX2_7-RX2/OUT1A") (pintype "bidirectional"))
      (node (ref "U3") (pin "17") (pinfunction "BIN1_17") (pintype "input"))
    )
    (net (code "18") (name "LMIN2") (class "Default")
      (node (ref "U$57") (pin "8-TX2/IN1") (pinfunction "8-IN1/TX2_8-TX2/IN1") (pintype "bidirectional"))
      (node (ref "U3") (pin "16") (pinfunction "BIN2_16") (pintype "input"))
    )
    (net (code "19") (name "LMOUT+") (class "Default")
      (node (ref "MOTORL") (pin "1") (pinfunction "1_1") (pintype "passive"))
      (node (ref "U3") (pin "11") (pinfunction "BOUT1_11") (pintype "output"))
      (node (ref "U3") (pin "12") (pinfunction "BOUT1_12") (pintype "output"))
    )
    (net (code "20") (name "LMOUT-") (class "Default")
      (node (ref "MOTORL") (pin "6") (pinfunction "6_6") (pintype "passive"))
      (node (ref "U3") (pin "7") (pinfunction "BOUT2_7") (pintype "output"))
      (node (ref "U3") (pin "8") (pinfunction "BOUT2_8") (pintype "output"))
    )
    (net (code "21") (name "Net-(C8-P$2)") (class "Default")
      (node (ref "C8") (pin "2") (pinfunction "P$2_2") (pintype "passive"))
      (node (ref "R14") (pin "2") (pinfunction "2_2") (pintype "passive"))
      (node (ref "R15") (pin "1") (pinfunction "1_1") (pintype "passive"))
      (node (ref "U$12") (pin "3") (pinfunction "FB_3") (pintype "bidirectional"))
    )
    (net (code "22") (name "Net-(CHRG-PadC)") (class "Default")
      (node (ref "CHRG") (pin "C") (pinfunction "C_C") (pintype "passive"))
      (node (ref "R121") (pin "2") (pinfunction "2_2") (pintype "passive"))
    )
    (net (code "23") (name "Net-(DONE-PadC)") (class "Default")
      (node (ref "DONE") (pin "C") (pinfunction "C_C") (pintype "passive"))
      (node (ref "R122") (pin "2") (pinfunction "2_2") (pintype "passive"))
    )
    (net (code "24") (name "Net-(L2-2)") (class "Default")
      (node (ref "L2") (pin "P$2") (pinfunction "2_P$2") (pintype "passive"))
      (node (ref "U$12") (pin "7") (pinfunction "SW_7") (pintype "bidirectional"))
    )
    (net (code "25") (name "Net-(L3-2)") (class "Default")
      (node (ref "L3") (pin "P$2") (pinfunction "2_P$2") (pintype "passive"))
      (node (ref "U1") (pin "1") (pinfunction "1_SW_1") (pintype "bidirectional"))
      (node (ref "U1") (pin "2") (pinfunction "2_SW_2") (pintype "bidirectional"))
    )
    (net (code "26") (name "Net-(LBO-PadA)") (class "Default")
      (node (ref "LBO") (pin "A") (pinfunction "A_A") (pintype "passive"))
      (node (ref "R21") (pin "1") (pinfunction "1_1") (pintype "passive"))
    )
    (net (code "27") (name "Net-(PWR-PadA)") (class "Default")
      (node (ref "PWR") (pin "A") (pinfunction "A_A") (pintype "passive"))
      (node (ref "R22") (pin "2") (pinfunction "2_2") (pintype "passive"))
    )
    (net (code "28") (name "Net-(R21-Pad2)") (class "Default")
      (node (ref "R21") (pin "2") (pinfunction "2_2") (pintype "passive"))
      (node (ref "T1") (pin "C") (pinfunction "C_C") (pintype "passive"))
    )
    (net (code "29") (name "Net-(R50-Pad2)") (class "Default")
      (node (ref "R50") (pin "2") (pinfunction "2_2") (pintype "passive"))
      (node (ref "TEENSY_POWER") (pin "C") (pinfunction "C_C") (pintype "passive"))
    )
    (net (code "30") (name "Net-(U$6-CAP)") (class "Default")
      (node (ref "C4") (pin "2") (pinfunction "2_2") (pintype "passive"))
      (node (ref "U$6") (pin "9") (pinfunction "CAP_9") (pintype "passive"))
    )
    (net (code "31") (name "Net-(U$6-XIN32)") (class "Default")
      (node (ref "C1") (pin "2") (pinfunction "2_2") (pintype "passive"))
      (node (ref "U$6") (pin "27") (pinfunction "XIN32_27") (pintype "input"))
      (node (ref "X2") (pin "P$2") (pinfunction "P$2_P$2") (pintype "bidirectional"))
    )
    (net (code "32") (name "Net-(U$6-XOUT32)") (class "Default")
      (node (ref "C2") (pin "2") (pinfunction "2_2") (pintype "passive"))
      (node (ref "U$6") (pin "26") (pinfunction "XOUT32_26") (pintype "output"))
      (node (ref "X2") (pin "P$1") (pinfunction "P$1_P$1") (pintype "bidirectional"))
    )
    (net (code "33") (name "Net-(U1-FB)") (class "Default")
      (node (ref "R24") (pin "1") (pinfunction "1_1") (pintype "passive"))
      (node (ref "R25") (pin "2") (pinfunction "2_2") (pintype "passive"))
      (node (ref "U1") (pin "12") (pinfunction "FB_12") (pintype "bidirectional"))
    )
    (net (code "34") (name "Net-(U1-LBI)") (class "Default")
      (node (ref "R26") (pin "2") (pinfunction "2_2") (pintype "passive"))
      (node (ref "R27") (pin "1") (pinfunction "1_1") (pintype "passive"))
      (node (ref "U1") (pin "7") (pinfunction "LBI_7") (pintype "bidirectional"))
    )
    (net (code "35") (name "Net-(U16-PROG1)") (class "Default")
      (node (ref "R123") (pin "2") (pinfunction "2_2") (pintype "passive"))
      (node (ref "U16") (pin "P$13") (pinfunction "PROG1_P$13") (pintype "bidirectional"))
    )
    (net (code "36") (name "Net-(U16-PROG3)") (class "Default")
      (node (ref "R124") (pin "2") (pinfunction "2_2") (pintype "passive"))
      (node (ref "U16") (pin "P$12") (pinfunction "PROG3_P$12") (pintype "bidirectional"))
    )
    (net (code "37") (name "Net-(U16-STAT1{slash}LBO)") (class "Default")
      (node (ref "R121") (pin "1") (pinfunction "1_1") (pintype "passive"))
      (node (ref "U16") (pin "P$8") (pinfunction "STAT1/LBO_P$8") (pintype "bidirectional"))
    )
    (net (code "38") (name "Net-(U16-STAT2)") (class "Default")
      (node (ref "R122") (pin "1") (pinfunction "1_1") (pintype "passive"))
      (node (ref "U16") (pin "P$7") (pinfunction "STAT2_P$7") (pintype "bidirectional"))
    )
    (net (code "39") (name "Net-(U16-THERM)") (class "Default")
      (node (ref "THERM6") (pin "2") (pinfunction "2_2") (pintype "passive"))
      (node (ref "U16") (pin "P$5") (pinfunction "THERM_P$5") (pintype "bidirectional"))
    )
    (net (code "40") (name "Net-(U16-VPCC)") (class "Default")
      (node (ref "R119") (pin "1") (pinfunction "1_1") (pintype "passive"))
      (node (ref "R120") (pin "1") (pinfunction "1_1") (pintype "passive"))
      (node (ref "U16") (pin "P$2") (pinfunction "VPCC_P$2") (pintype "bidirectional"))
    )
    (net (code "41") (name "PS0_3V") (class "Default")
      (node (ref "R3") (pin "3") (pinfunction "1_3") (pintype "passive"))
      (node (ref "U$6") (pin "6") (pinfunction "PS0_6") (pintype "input"))
    )
    (net (code "42") (name "PS1_3V") (class "Default")
      (node (ref "R3") (pin "4") (pinfunction "1_4") (pintype "passive"))
      (node (ref "U$6") (pin "5") (pinfunction "PS1_5") (pintype "input"))
    )
    (net (code "43") (name "PWML") (class "Default")
      (node (ref "U$57") (pin "23-A9/CRX1/CCLK1") (pinfunction "23-A9/CRX1/MCLK1_23-A9/CRX1/CCLK1") (pintype "bidirectional"))
      (node (ref "U3") (pin "15") (pinfunction "PWMB_15") (pintype "input"))
    )
    (net (code "44") (name "PWMR") (class "Default")
      (node (ref "U$57") (pin "4-BCLK2") (pinfunction "4-BCLK1_4-BCLK2") (pintype "bidirectional"))
      (node (ref "U3") (pin "23") (pinfunction "PWMA_23") (pintype "input"))
    )
    (net (code "45") (name "RMIN1") (class "Default")
      (node (ref "U$57") (pin "0-RX1") (pinfunction "0-RX1/CRX2_0-RX1") (pintype "bidirectional"))
      (node (ref "U3") (pin "21") (pinfunction "AIN1_21") (pintype "input"))
    )
    (net (code "46") (name "RMIN2") (class "Default")
      (node (ref "U$57") (pin "1-TX1") (pinfunction "1-TX1/CTX2_1-TX1") (pintype "bidirectional"))
      (node (ref "U3") (pin "22") (pinfunction "AIN2_22") (pintype "input"))
    )
    (net (code "47") (name "RMOUT+") (class "Default")
      (node (ref "MOTORR") (pin "1") (pinfunction "1_1") (pintype "passive"))
      (node (ref "U3") (pin "1") (pinfunction "AOUT1_1") (pintype "output"))
      (node (ref "U3") (pin "2") (pinfunction "AOUT1_2") (pintype "output"))
    )
    (net (code "48") (name "RMOUT-") (class "Default")
      (node (ref "MOTORR") (pin "6") (pinfunction "6_6") (pintype "passive"))
      (node (ref "U3") (pin "5") (pinfunction "AOUT2_5") (pintype "output"))
      (node (ref "U3") (pin "6") (pinfunction "AOUT2_6") (pintype "output"))
    )
    (net (code "49") (name "RPI_RX") (class "Default")
      (node (ref "J4") (pin "1") (pinfunction "1_1") (pintype "passive"))
      (node (ref "U$57") (pin "14-A0/TX3/S-PFI_OUT") (pinfunction "14-A0/TX3/S-PDIF_IN_14-A0/TX3/S-PFI_OUT") (pintype "bidirectional"))
    )
    (net (code "50") (name "RPI_TX") (class "Default")
      (node (ref "J4") (pin "2") (pinfunction "2_2") (pintype "passive"))
      (node (ref "U$57") (pin "15-A1/RX3/S-PDIF_IN") (pinfunction "15-A1/RX3/SPDIF_IN_15-A1/RX3/S-PDIF_IN") (pintype "bidirectional"))
    )
    (net (code "51") (name "SCL0") (class "Default")
      (node (ref "JD0") (pin "4") (pinfunction "4_4") (pintype "passive"))
      (node (ref "R29") (pin "2") (pinfunction "2_2") (pintype "passive"))
      (node (ref "U5") (pin "5") (pinfunction "SC0_5") (pintype "bidirectional"))
    )
    (net (code "52") (name "SCL1") (class "Default")
      (node (ref "JD1") (pin "4") (pinfunction "4_4") (pintype "passive"))
      (node (ref "R31") (pin "2") (pinfunction "2_2") (pintype "passive"))
      (node (ref "U5") (pin "7") (pinfunction "SC1_7") (pintype "bidirectional"))
    )
    (net (code "53") (name "SCL2") (class "Default")
      (node (ref "JD2") (pin "4") (pinfunction "4_4") (pintype "passive"))
      (node (ref "R33") (pin "2") (pinfunction "2_2") (pintype "passive"))
      (node (ref "U5") (pin "9") (pinfunction "SC2_9") (pintype "bidirectional"))
    )
    (net (code "54") (name "SCL3") (class "Default")
      (node (ref "JD3") (pin "4") (pinfunction "4_4") (pintype "passive"))
      (node (ref "R35") (pin "2") (pinfunction "2_2") (pintype "passive"))
      (node (ref "U5") (pin "11") (pinfunction "SC3_11") (pintype "bidirectional"))
    )
    (net (code "55") (name "SCL4") (class "Default")
      (node (ref "JD4") (pin "4") (pinfunction "4_4") (pintype "passive"))
      (node (ref "R37") (pin "2") (pinfunction "2_2") (pintype "passive"))
      (node (ref "U5") (pin "14") (pinfunction "SC4_14") (pintype "bidirectional"))
    )
    (net (code "56") (name "SCL5") (class "Default")
      (node (ref "JD5") (pin "4") (pinfunction "4_4") (pintype "passive"))
      (node (ref "R39") (pin "2") (pinfunction "2_2") (pintype "passive"))
      (node (ref "U5") (pin "16") (pinfunction "SC5_16") (pintype "bidirectional"))
    )
    (net (code "57") (name "SCL6") (class "Default")
      (node (ref "JD6") (pin "4") (pinfunction "4_4") (pintype "passive"))
      (node (ref "R41") (pin "2") (pinfunction "2_2") (pintype "passive"))
      (node (ref "U5") (pin "18") (pinfunction "SC6_18") (pintype "bidirectional"))
    )
    (net (code "58") (name "SCL_MAIN") (class "Default")
      (node (ref "IC1") (pin "9") (pinfunction "SCL_9") (pintype "bidirectional"))
      (node (ref "R9") (pin "8") (pinfunction "2_8") (pintype "passive"))
      (node (ref "U$57") (pin "19-A5/SCL0") (pinfunction "19-A5/SCL0_19-A5/SCL0") (pintype "bidirectional"))
      (node (ref "U$6") (pin "19") (pinfunction "COM1/SCL/RX_19") (pintype "bidirectional"))
      (node (ref "U5") (pin "22") (pinfunction "SCL_22") (pintype "bidirectional"))
    )
    (net (code "59") (name "SDA0") (class "Default")
      (node (ref "JD0") (pin "3") (pinfunction "3_3") (pintype "passive"))
      (node (ref "R28") (pin "2") (pinfunction "2_2") (pintype "passive"))
      (node (ref "U5") (pin "4") (pinfunction "SD0_4") (pintype "bidirectional"))
    )
    (net (code "60") (name "SDA1") (class "Default")
      (node (ref "JD1") (pin "3") (pinfunction "3_3") (pintype "passive"))
      (node (ref "R30") (pin "2") (pinfunction "2_2") (pintype "passive"))
      (node (ref "U5") (pin "6") (pinfunction "SD1_6") (pintype "bidirectional"))
    )
    (net (code "61") (name "SDA2") (class "Default")
      (node (ref "JD2") (pin "3") (pinfunction "3_3") (pintype "passive"))
      (node (ref "R32") (pin "2") (pinfunction "2_2") (pintype "passive"))
      (node (ref "U5") (pin "8") (pinfunction "SD2_8") (pintype "bidirectional"))
    )
    (net (code "62") (name "SDA3") (class "Default")
      (node (ref "JD3") (pin "3") (pinfunction "3_3") (pintype "passive"))
      (node (ref "R34") (pin "2") (pinfunction "2_2") (pintype "passive"))
      (node (ref "U5") (pin "10") (pinfunction "SD3_10") (pintype "bidirectional"))
    )
    (net (code "63") (name "SDA4") (class "Default")
      (node (ref "JD4") (pin "3") (pinfunction "3_3") (pintype "passive"))
      (node (ref "R36") (pin "2") (pinfunction "2_2") (pintype "passive"))
      (node (ref "U5") (pin "13") (pinfunction "SD4_13") (pintype "bidirectional"))
    )
    (net (code "64") (name "SDA5") (class "Default")
      (node (ref "JD5") (pin "3") (pinfunction "3_3") (pintype "passive"))
      (node (ref "R38") (pin "2") (pinfunction "2_2") (pintype "passive"))
      (node (ref "U5") (pin "15") (pinfunction "SD5_15") (pintype "bidirectional"))
    )
    (net (code "65") (name "SDA6") (class "Default")
      (node (ref "JD6") (pin "3") (pinfunction "3_3") (pintype "passive"))
      (node (ref "R40") (pin "2") (pinfunction "2_2") (pintype "passive"))
      (node (ref "U5") (pin "17") (pinfunction "SD6_17") (pintype "bidirectional"))
    )
    (net (code "66") (name "SDA_MAIN") (class "Default")
      (node (ref "IC1") (pin "8") (pinfunction "SDA_8") (pintype "bidirectional"))
      (node (ref "R9") (pin "5") (pinfunction "2_5") (pintype "passive"))
      (node (ref "U$57") (pin "18-A4/SDA0") (pinfunction "18-A4/SDA0_18-A4/SDA0") (pintype "bidirectional"))
      (node (ref "U$6") (pin "20") (pinfunction "COM0/SDA/TX_20") (pintype "bidirectional"))
      (node (ref "U5") (pin "23") (pinfunction "SDA_23") (pintype "bidirectional"))
    )
    (net (code "67") (name "STBY") (class "Default")
      (node (ref "R16") (pin "1") (pinfunction "1_1") (pintype "passive"))
      (node (ref "U3") (pin "19") (pinfunction "STBY_19") (pintype "input"))
    )
    (net (code "68") (name "VBAT") (class "Default")
      (node (ref "C13") (pin "1") (pinfunction "1_1") (pintype "passive"))
      (node (ref "C15") (pin "1") (pinfunction "1_1") (pintype "passive"))
      (node (ref "C3") (pin "1") (pinfunction "P$1_1") (pintype "passive"))
      (node (ref "C7") (pin "1") (pinfunction "P$1_1") (pintype "passive"))
      (node (ref "IC1") (pin "14") (pinfunction "IN-_14") (pintype "bidirectional"))
      (node (ref "IC1") (pin "15") (pinfunction "IN-_15") (pintype "bidirectional"))
      (node (ref "IC1") (pin "16") (pinfunction "IN-_16") (pintype "bidirectional"))
      (node (ref "JP1") (pin "2") (pinfunction "2_2") (pintype "passive"))
      (node (ref "L2") (pin "P$1") (pinfunction "1_P$1") (pintype "passive"))
      (node (ref "L3") (pin "P$1") (pinfunction "1_P$1") (pintype "passive"))
      (node (ref "R1") (pin "1") (pinfunction "1_1") (pintype "passive"))
      (node (ref "R11") (pin "2") (pinfunction "2_2") (pintype "passive"))
      (node (ref "R27") (pin "2") (pinfunction "2_2") (pintype "passive"))
      (node (ref "T1") (pin "E") (pinfunction "E_E") (pintype "passive"))
      (node (ref "U$12") (pin "4") (pinfunction "ILIM_4") (pintype "bidirectional"))
      (node (ref "U$12") (pin "8") (pinfunction "VIN_8") (pintype "bidirectional"))
      (node (ref "U1") (pin "6") (pinfunction "VBAT_6") (pintype "bidirectional"))
    )
    (net (code "69") (name "VBAT_IN") (class "Default")
      (node (ref "IC1") (pin "1") (pinfunction "IN+_1") (pintype "bidirectional"))
      (node (ref "IC1") (pin "12") (pinfunction "VBUS_12") (pintype "power_in"))
      (node (ref "IC1") (pin "2") (pinfunction "IN+_2") (pintype "bidirectional"))
      (node (ref "IC1") (pin "3") (pinfunction "IN+_3") (pintype "bidirectional"))
      (node (ref "JP1") (pin "1") (pinfunction "1_1") (pintype "passive"))
      (node (ref "U16") (pin "P$1") (pinfunction "VOUT1_P$1") (pintype "bidirectional"))
      (node (ref "U16") (pin "P$20") (pinfunction "VOUT2_P$20") (pintype "bidirectional"))
    )
    (net (code "70") (name "VBAT_MEASURE") (class "Default")
      (node (ref "R11") (pin "1") (pinfunction "1_1") (pintype "passive"))
      (node (ref "R12") (pin "2") (pinfunction "2_2") (pintype "passive"))
      (node (ref "U$57") (pin "22-A8/CTX1") (pinfunction "22-A8/CTX1_22-A8/CTX1") (pintype "bidirectional"))
    )
    (net (code "71") (name "VBUS") (class "Default")
      (node (ref "C17") (pin "1") (pinfunction "1_1") (pintype "passive"))
      (node (ref "CHRG") (pin "A") (pinfunction "A_A") (pintype "passive"))
      (node (ref "CN4") (pin "VBUS") (pinfunction "VBUS_VBUS") (pintype "power_in"))
      (node (ref "DONE") (pin "A") (pinfunction "A_A") (pintype "passive"))
      (node (ref "R119") (pin "2") (pinfunction "2_2") (pintype "passive"))
      (node (ref "R13") (pin "1") (pinfunction "1_1") (pintype "passive"))
      (node (ref "U16") (pin "P$17") (pinfunction "CE_P$17") (pintype "bidirectional"))
      (node (ref "U16") (pin "P$18") (pinfunction "VIN1_P$18") (pintype "bidirectional"))
      (node (ref "U16") (pin "P$19") (pinfunction "VIN2_P$19") (pintype "bidirectional"))
      (node (ref "U16") (pin "P$3") (pinfunction "SEL_P$3") (pintype "bidirectional"))
      (node (ref "U16") (pin "P$4") (pinfunction "PROG2_P$4") (pintype "bidirectional"))
      (node (ref "U16") (pin "P$9") (pinfunction "/TE_P$9") (pintype "bidirectional"))
    )
    (net (code "72") (name "VLIPO") (class "Default")
      (node (ref "B1") (pin "2") (pinfunction "+_2") (pintype "passive"))
      (node (ref "C49") (pin "1") (pinfunction "1_1") (pintype "passive"))
      (node (ref "U16") (pin "P$14") (pinfunction "VBAT1_P$14") (pintype "bidirectional"))
      (node (ref "U16") (pin "P$15") (pinfunction "VBAT2_P$15") (pintype "bidirectional"))
      (node (ref "U16") (pin "P$16") (pinfunction "VBATSENS_P$16") (pintype "bidirectional"))
    )
    (net (code "73") (name "VMOTOR") (class "Default")
      (node (ref "C11") (pin "1") (pinfunction "P$1_1") (pintype "passive"))
      (node (ref "Q2") (pin "2") (pinfunction "S_2") (pintype "passive"))
      (node (ref "U3") (pin "13") (pinfunction "VM_13") (pintype "power_in"))
      (node (ref "U3") (pin "14") (pinfunction "VM_14") (pintype "power_in"))
      (node (ref "U3") (pin "24") (pinfunction "VM_24") (pintype "power_in"))
    )
    (net (code "74") (name "unconnected-(CN4-PadD+)") (class "Default")
      (node (ref "CN4") (pin "D+") (pinfunction "D+_D+") (pintype "bidirectional"))
    )
    (net (code "75") (name "unconnected-(CN4-PadD-)") (class "Default")
      (node (ref "CN4") (pin "D-") (pinfunction "D-_D-") (pintype "bidirectional"))
    )
    (net (code "76") (name "unconnected-(CN4-PadID)") (class "Default")
      (node (ref "CN4") (pin "ID") (pinfunction "ID_ID") (pintype "bidirectional"))
    )
    (net (code "77") (name "unconnected-(S1-NC-Pad1)") (class "Default")
      (node (ref "S1") (pin "1") (pinfunction "NC_1") (pintype "no_connect"))
    )
    (net (code "78") (name "unconnected-(U$6-PIN7(SWDIO)-Pad7)") (class "Default")
      (node (ref "U$6") (pin "7") (pinfunction "PIN7(SWDIO)_7") (pintype "bidirectional"))
    )
    (net (code "79") (name "unconnected-(U$57-10-CS-Pad10-CS{slash}MQSR)") (class "Default")
      (node (ref "U$57") (pin "10-CS/MQSR") (pinfunction "10-CS_10-CS/MQSR") (pintype "bidirectional"))
    )
    (net (code "80") (name "unconnected-(U$57-12-MISO{slash}MQSL-Pad12-MIO{slash}MQSL)") (class "Default")
      (node (ref "U$57") (pin "12-MIO/MQSL") (pinfunction "12-MISO/MQSL_12-MIO/MQSL") (pintype "bidirectional"))
    )
    (net (code "81") (name "unconnected-(U$57-25-A11{slash}RX6{slash}SDA2-Pad25-A11{slash}SDA2)") (class "Default")
      (node (ref "U$57") (pin "25-A11/SDA2") (pinfunction "25-A11/RX6/SDA2_25-A11/SDA2") (pintype "bidirectional"))
    )
    (net (code "82") (name "unconnected-(U$57-32-OUT1B-Pad32-OUTB1)") (class "Default")
      (node (ref "U$57") (pin "32-OUTB1") (pinfunction "32-OUT1B_32-OUTB1") (pintype "bidirectional"))
    )
    (net (code "83") (name "unconnected-(U$57-Pad3V3-2)") (class "Default")
      (node (ref "U$57") (pin "3V3-2") (pinfunction "3V3-2_3V3-2") (pintype "bidirectional"))
    )
    (net (code "84") (name "unconnected-(U$57-Pad5-IN2)") (class "Default")
      (node (ref "U$57") (pin "5-IN2") (pinfunction "5-IN2_5-IN2") (pintype "bidirectional"))
    )
    (net (code "85") (name "unconnected-(U$57-Pad6-OUT1D)") (class "Default")
      (node (ref "U$57") (pin "6-OUT1D") (pinfunction "6-OUT1D_6-OUT1D") (pintype "bidirectional"))
    )
    (net (code "86") (name "unconnected-(U$57-Pad9-OUT1C)") (class "Default")
      (node (ref "U$57") (pin "9-OUT1C") (pinfunction "9-OUT1C_9-OUT1C") (pintype "bidirectional"))
    )
    (net (code "87") (name "unconnected-(U$57-Pad11-MOSI{slash}CTX1)") (class "Default")
      (node (ref "U$57") (pin "11-MOSI/CTX1") (pinfunction "11-MOSI/CTX1_11-MOSI/CTX1") (pintype "bidirectional"))
    )
    (net (code "88") (name "unconnected-(U$57-Pad24-A10{slash}TX6{slash}SCL2)") (class "Default")
      (node (ref "U$57") (pin "24-A10/TX6/SCL2") (pinfunction "24-A10/TX6/SCL2_24-A10/TX6/SCL2") (pintype "bidirectional"))
    )
    (net (code "89") (name "unconnected-(U$57-Pad26-A12{slash}MOSI1)") (class "Default")
      (node (ref "U$57") (pin "26-A12/MOSI1") (pinfunction "26-A12/MOSI1_26-A12/MOSI1") (pintype "bidirectional"))
    )
    (net (code "90") (name "unconnected-(U$57-Pad27-A13{slash}SCK1)") (class "Default")
      (node (ref "U$57") (pin "27-A13/SCK1") (pinfunction "27-A13/SCK1_27-A13/SCK1") (pintype "bidirectional"))
    )
    (net (code "91") (name "unconnected-(U$57-Pad28-RX7)") (class "Default")
      (node (ref "U$57") (pin "28-RX7") (pinfunction "28-RX7_28-RX7") (pintype "bidirectional"))
    )
    (net (code "92") (name "unconnected-(U$57-Pad29-TX7)") (class "Default")
      (node (ref "U$57") (pin "29-TX7") (pinfunction "29-TX7_29-TX7") (pintype "bidirectional"))
    )
    (net (code "93") (name "unconnected-(U$57-Pad30-CRX3)") (class "Default")
      (node (ref "U$57") (pin "30-CRX3") (pinfunction "30-CRX3_30-CRX3") (pintype "bidirectional"))
    )
    (net (code "94") (name "unconnected-(U$57-Pad31-CTX3)") (class "Default")
      (node (ref "U$57") (pin "31-CTX3") (pinfunction "31-CTX3_31-CTX3") (pintype "bidirectional"))
    )
    (net (code "95") (name "unconnected-(U$57-Pad33-MCLK2)") (class "Default")
      (node (ref "U$57") (pin "33-MCLK2") (pinfunction "33-MCLK2_33-MCLK2") (pintype "bidirectional"))
    )
    (net (code "96") (name "unconnected-(U$57-PadON{slash}OFF)") (class "Default")
      (node (ref "U$57") (pin "ON/OFF") (pinfunction "ON/OFF_ON/OFF") (pintype "bidirectional"))
    )
    (net (code "97") (name "unconnected-(U$57-PadPROGRAM)") (class "Default")
      (node (ref "U$57") (pin "PROGRAM") (pinfunction "PROGRAM_PROGRAM") (pintype "bidirectional"))
    )
    (net (code "98") (name "unconnected-(U$57-PadVBAT)") (class "Default")
      (node (ref "U$57") (pin "VBAT") (pinfunction "VBAT_VBAT") (pintype "bidirectional"))
    )
    (net (code "99") (name "unconnected-(U$57-PadVUSB)") (class "Default")
      (node (ref "U$57") (pin "VUSB") (pinfunction "VUSB_VUSB") (pintype "bidirectional"))
    )
    (net (code "100") (name "unconnected-(U5-SC7-Pad20)") (class "Default")
      (node (ref "U5") (pin "20") (pinfunction "SC7_20") (pintype "bidirectional"))
    )
    (net (code "101") (name "unconnected-(U5-SD7-Pad19)") (class "Default")
      (node (ref "U5") (pin "19") (pinfunction "SD7_19") (pintype "bidirectional"))
    )
    (net (code "102") (name "unconnected-(U16-{slash}PG-PadP$6)") (class "Default")
      (node (ref "U16") (pin "P$6") (pinfunction "/PG_P$6") (pintype "bidirectional"))
    )
  )
)
